# motor_board_tmc.net
KiCad netlist of a schematic drawn in EAGLE
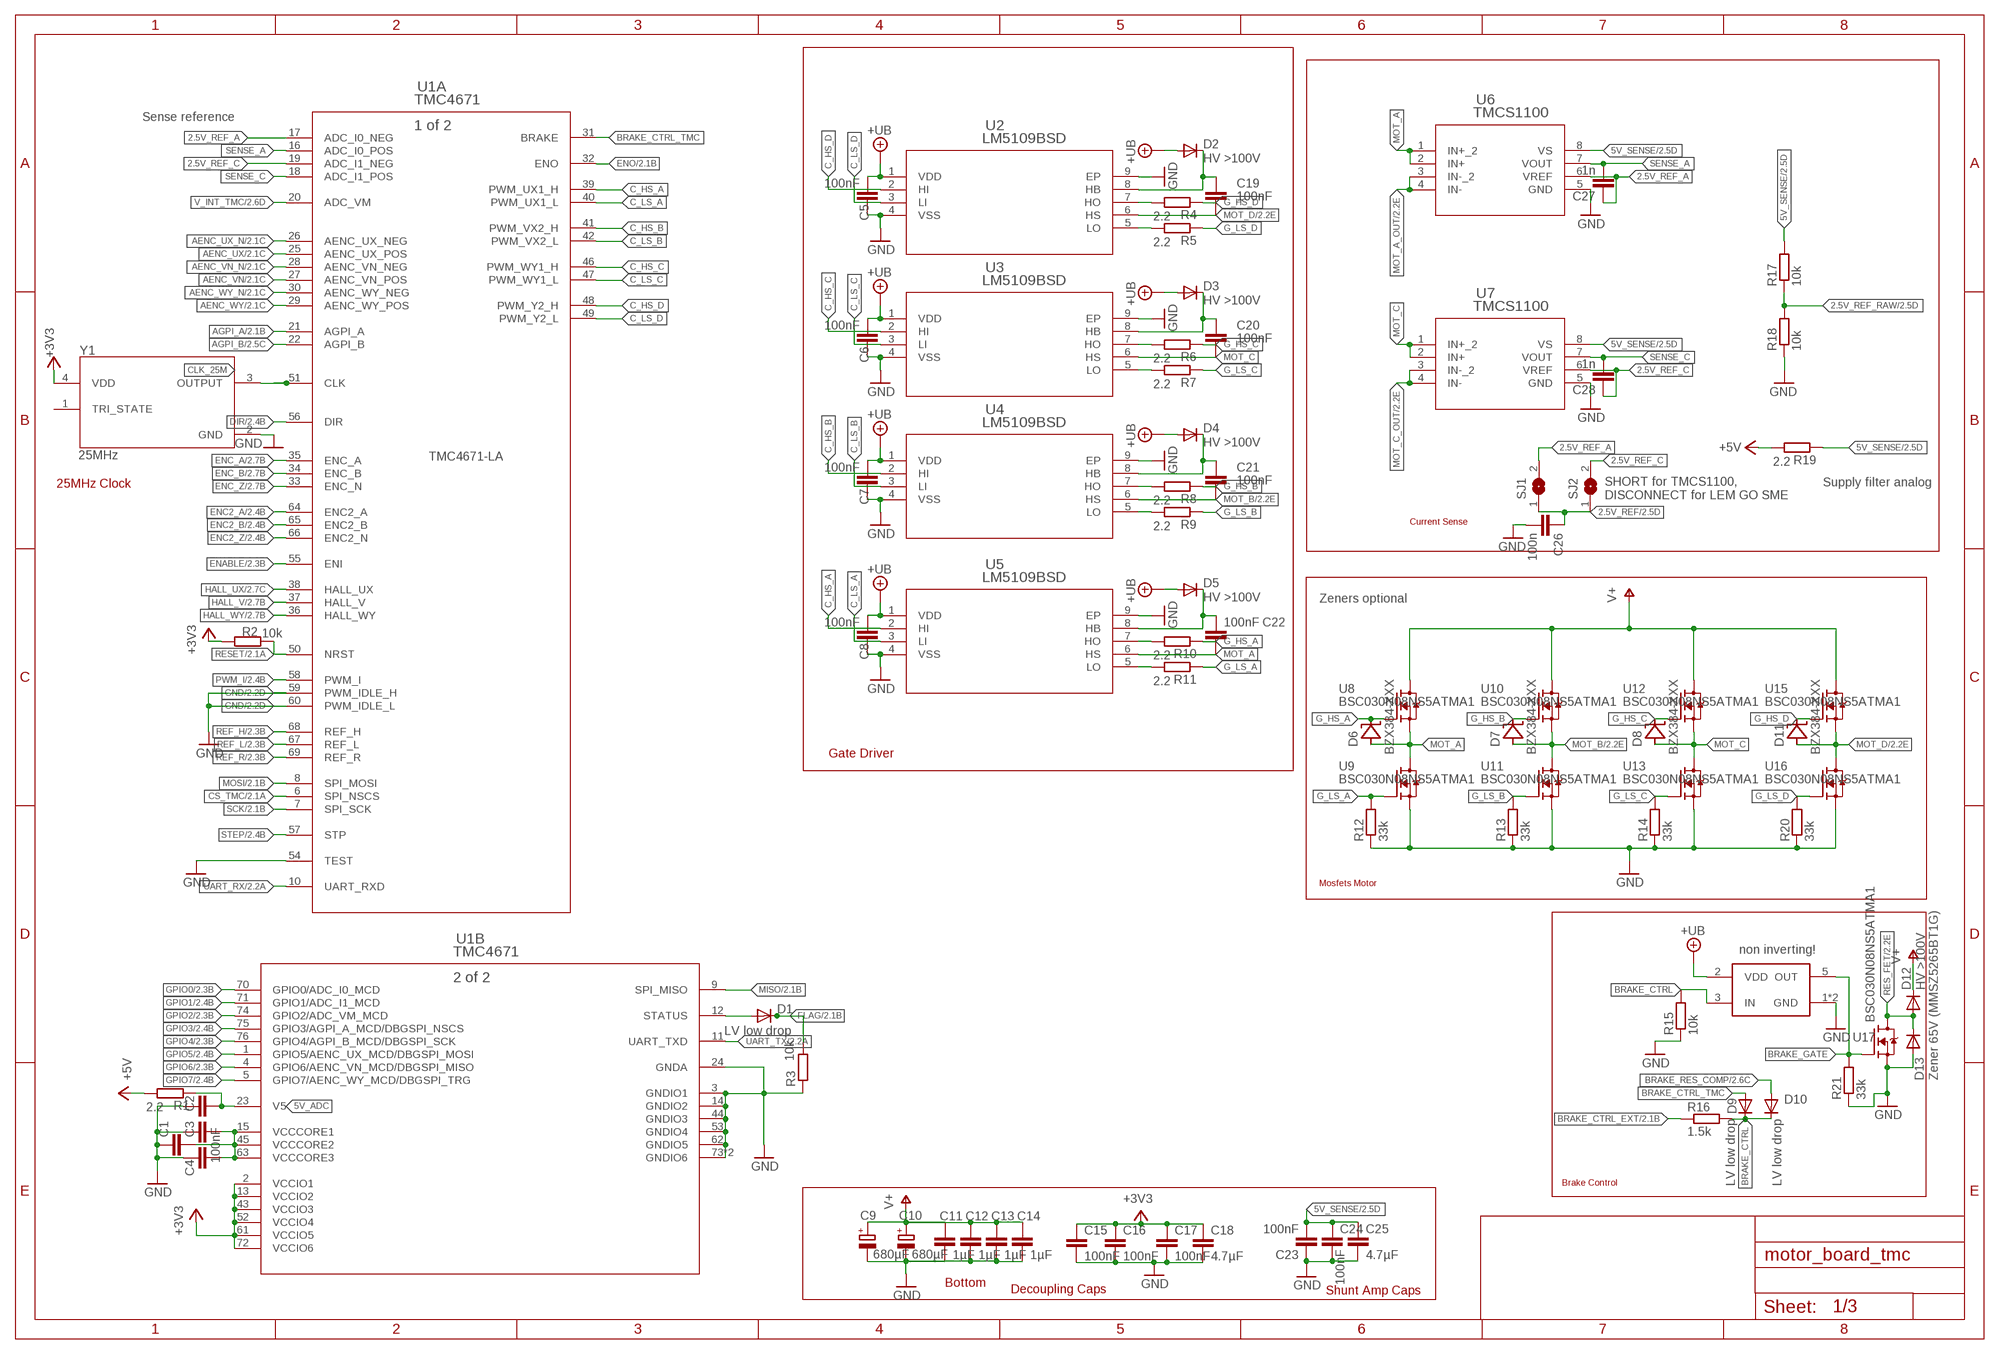
[diagram p0: schematic, sheet 1]
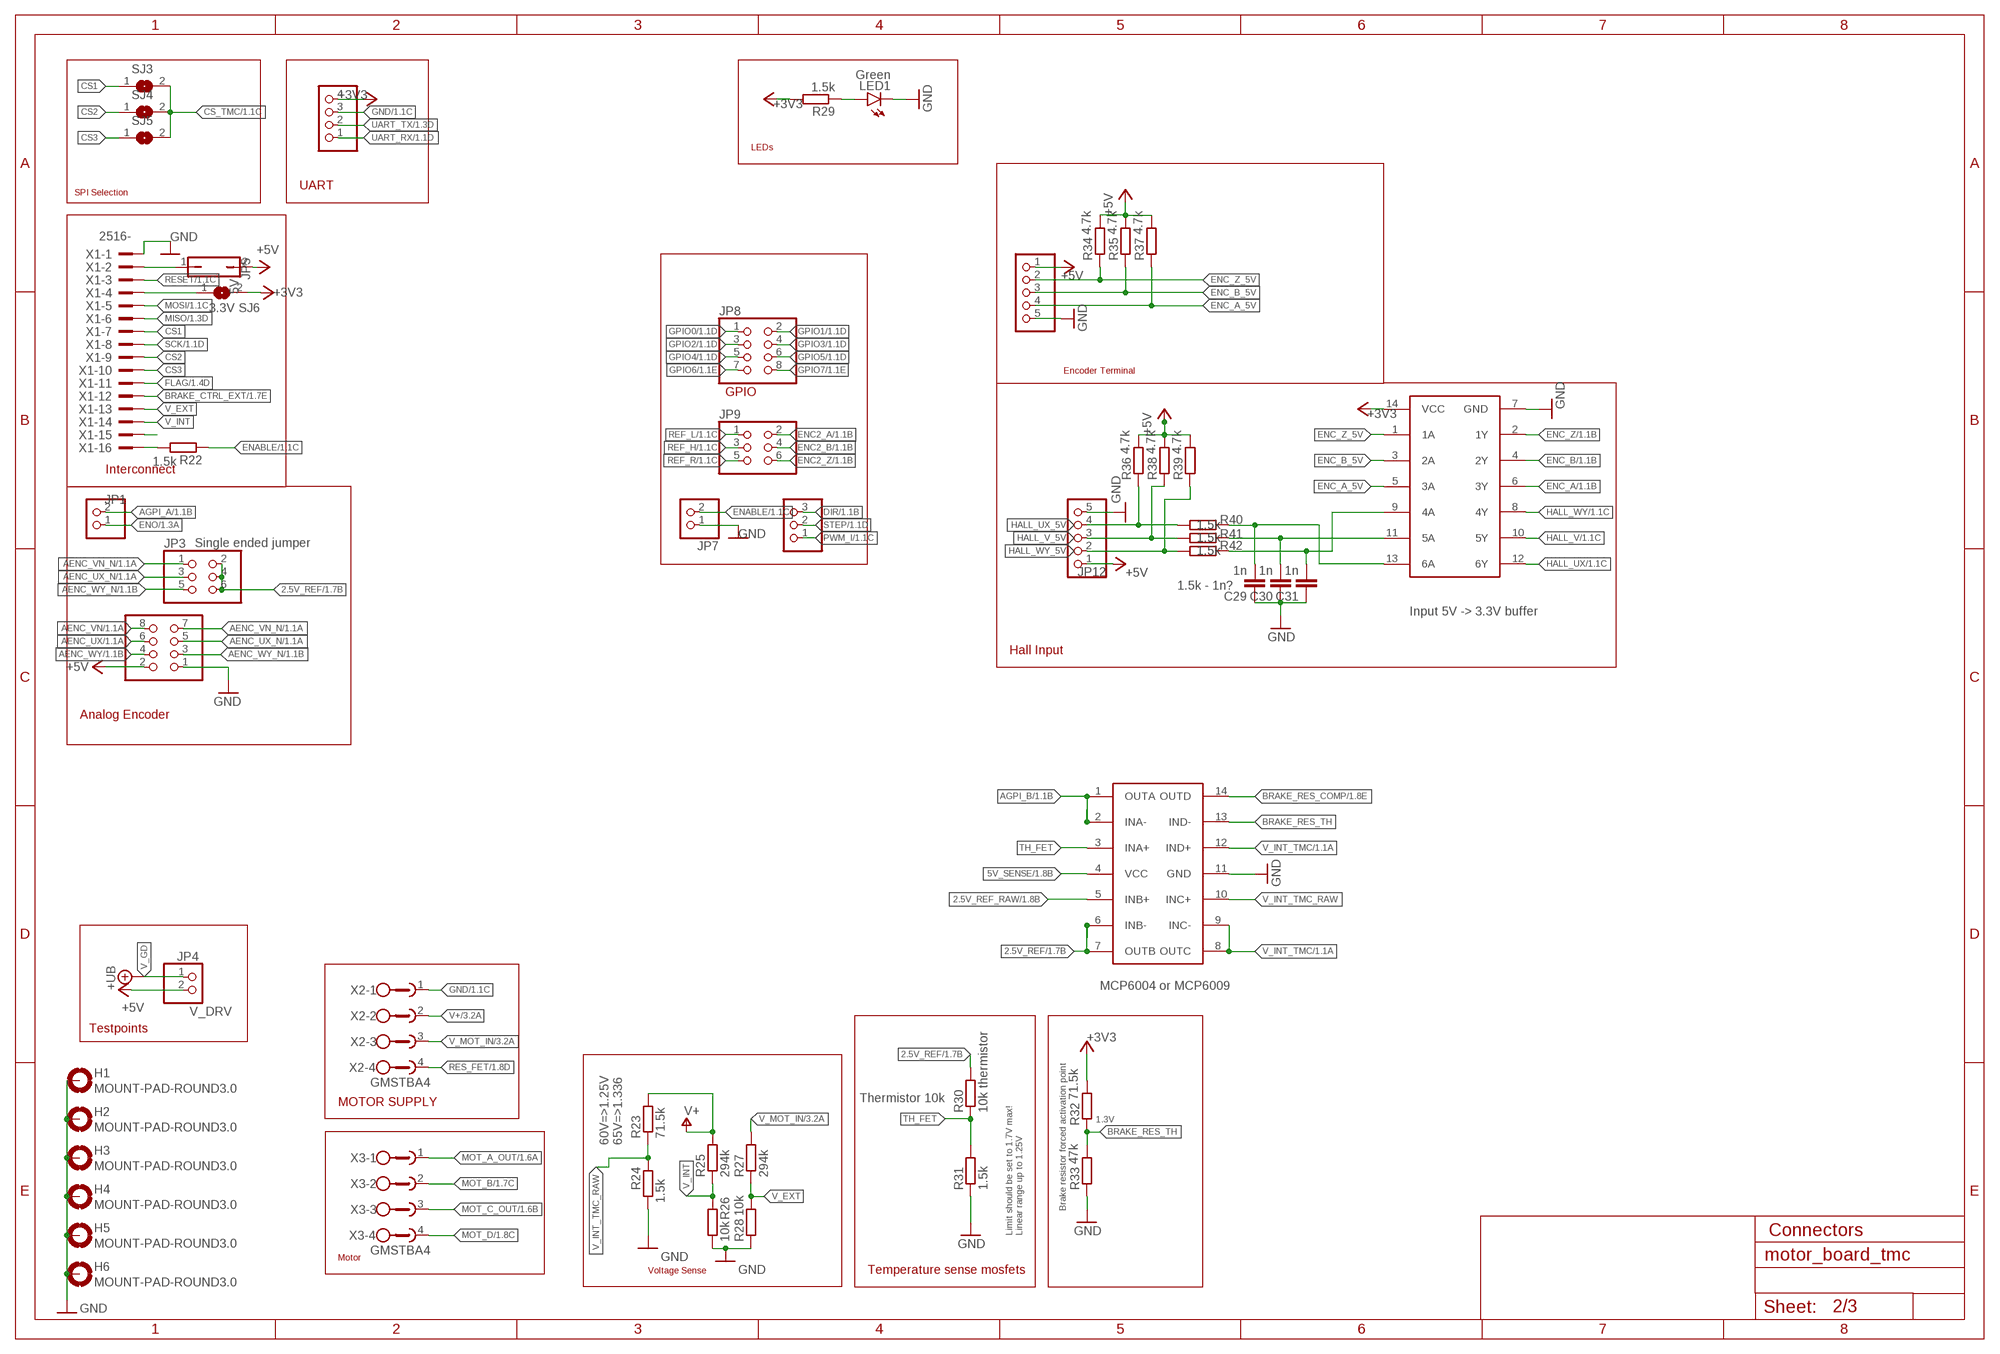
[diagram p1: schematic, sheet 2]
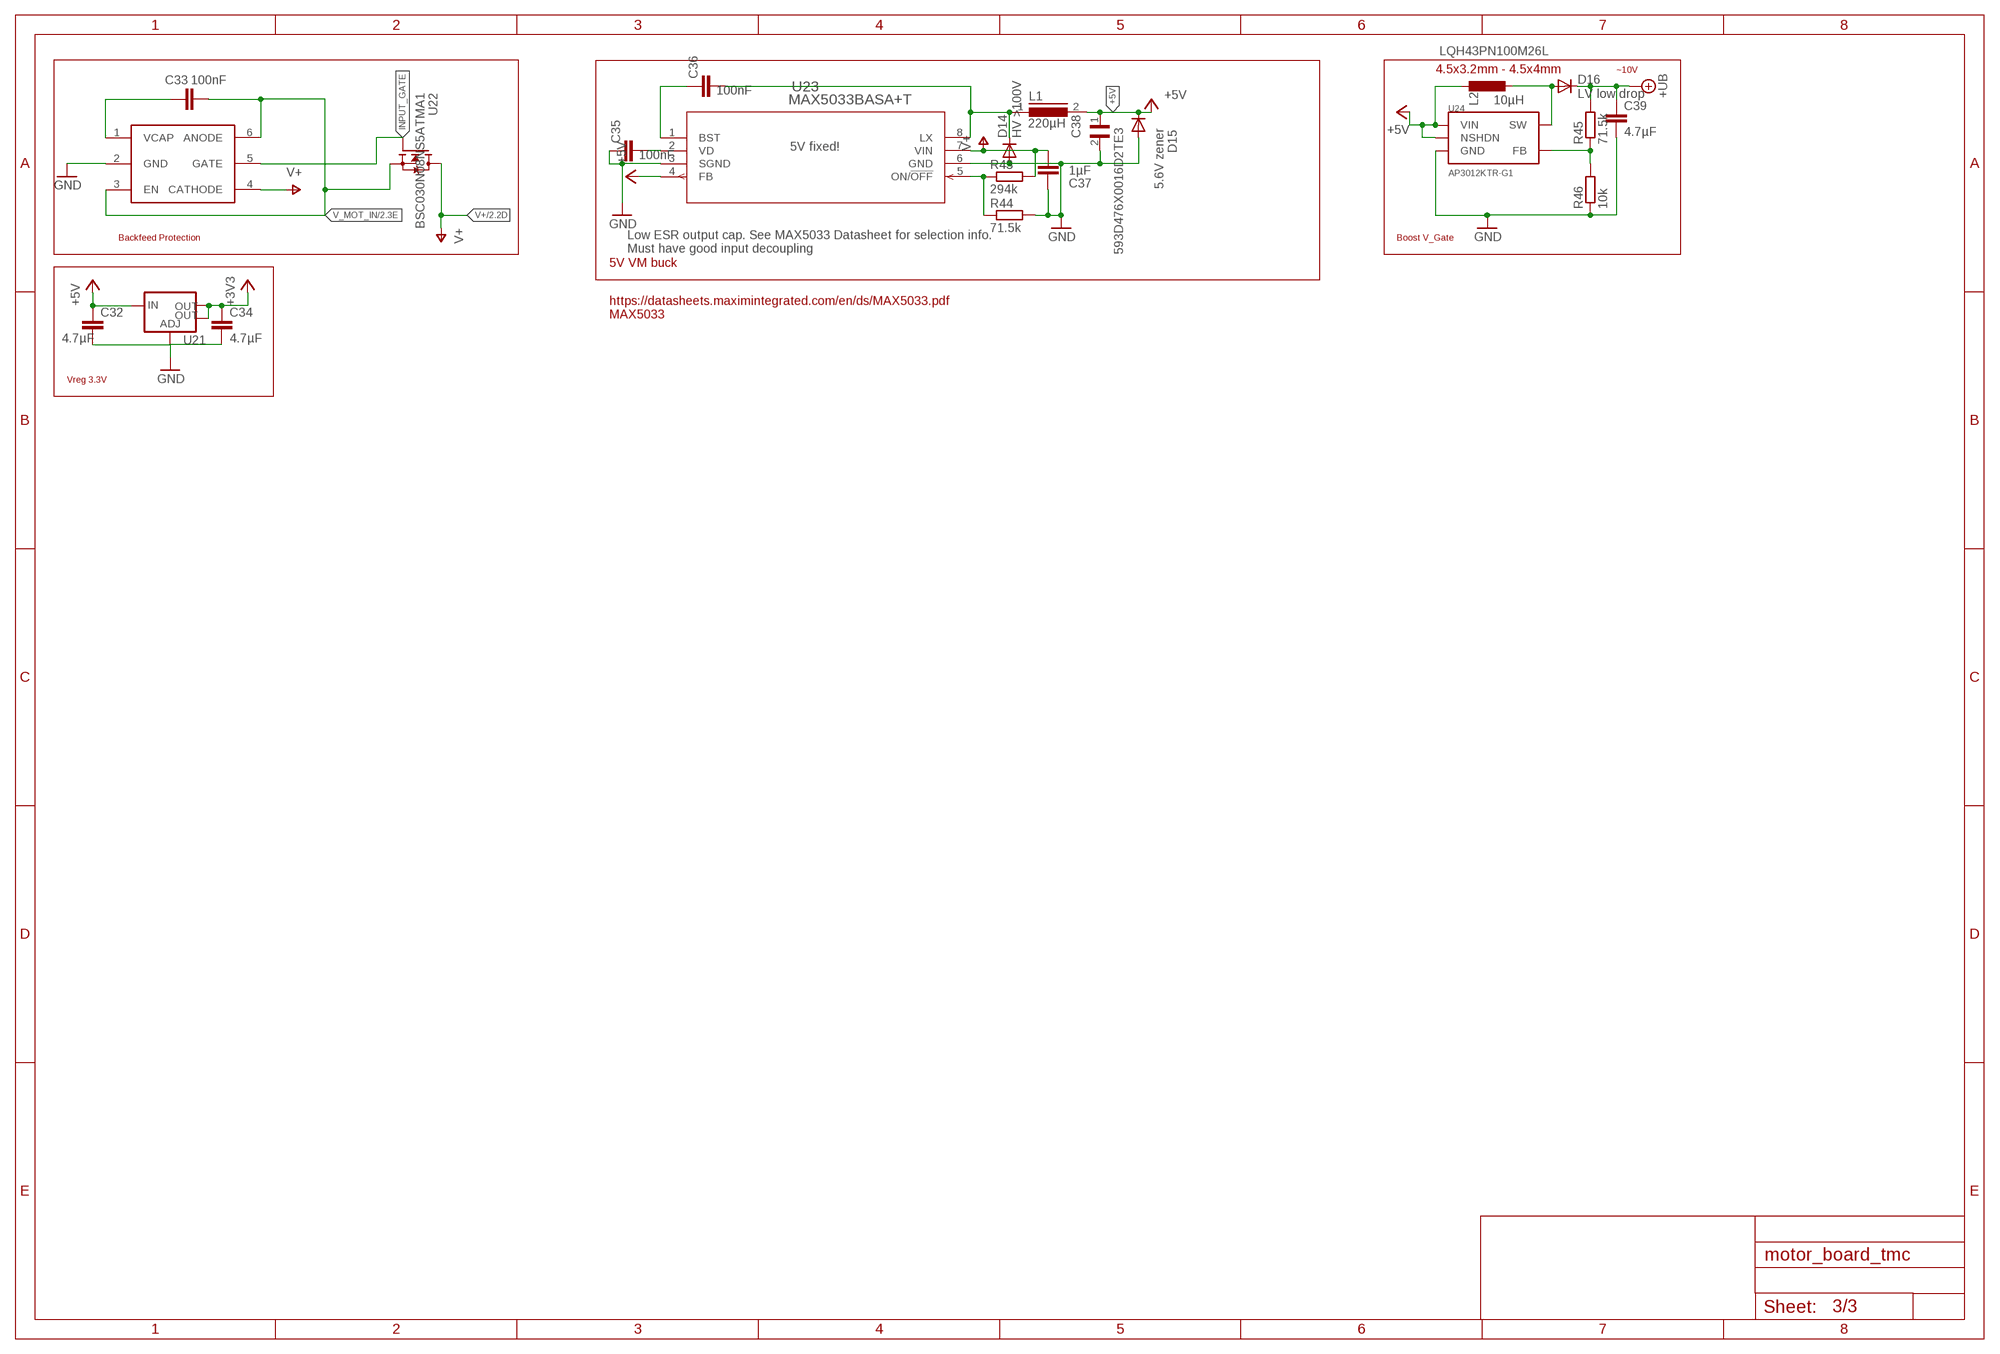
[diagram p2: schematic, sheet 3]

(export (version "E")
  (design (tool "Eeschema 10.0.6"))
  (components
    (comp (ref "C1")
      (value "100nF")
      (footprint "eagle-import:C0603")
      (libsource (lib "eagle-import") (part "C-EUC0603"))
    )
    (comp (ref "C2")
      (value "100nF")
      (footprint "eagle-import:C0603")
      (libsource (lib "eagle-import") (part "C-EUC0603"))
    )
    (comp (ref "C3")
      (value "100nF")
      (footprint "eagle-import:C0603")
      (libsource (lib "eagle-import") (part "C-EUC0603"))
    )
    (comp (ref "C4")
      (value "100nF")
      (footprint "eagle-import:C0603")
      (libsource (lib "eagle-import") (part "C-EUC0603"))
    )
    (comp (ref "C5")
      (value "100nF")
      (footprint "eagle-import:C0603")
      (libsource (lib "eagle-import") (part "C-EUC0603"))
    )
    (comp (ref "C6")
      (value "100nF")
      (footprint "eagle-import:C0603")
      (libsource (lib "eagle-import") (part "C-EUC0603"))
    )
    (comp (ref "C7")
      (value "100nF")
      (footprint "eagle-import:C0603")
      (libsource (lib "eagle-import") (part "C-EUC0603"))
    )
    (comp (ref "C8")
      (value "100nF")
      (footprint "eagle-import:C0603")
      (libsource (lib "eagle-import") (part "C-EUC0603"))
    )
    (comp (ref "C9")
      (value "680µF")
      (footprint "eagle-import:E7,5-16")
      (libsource (lib "eagle-import") (part "CPOL-EUE7.5-16"))
    )
    (comp (ref "C10")
      (value "680µF")
      (footprint "eagle-import:E7,5-16")
      (libsource (lib "eagle-import") (part "CPOL-EUE7.5-16"))
    )
    (comp (ref "C11")
      (value "1µF")
      (footprint "eagle-import:C1206")
      (libsource (lib "eagle-import") (part "C-EUC1206"))
    )
    (comp (ref "C12")
      (value "1µF")
      (footprint "eagle-import:C1206")
      (libsource (lib "eagle-import") (part "C-EUC1206"))
    )
    (comp (ref "C13")
      (value "1µF")
      (footprint "eagle-import:C1206")
      (libsource (lib "eagle-import") (part "C-EUC1206"))
    )
    (comp (ref "C14")
      (value "1µF")
      (footprint "eagle-import:C1206")
      (libsource (lib "eagle-import") (part "C-EUC1206"))
    )
    (comp (ref "C15")
      (value "100nF")
      (footprint "eagle-import:C0603")
      (libsource (lib "eagle-import") (part "C-EUC0603"))
    )
    (comp (ref "C16")
      (value "100nF")
      (footprint "eagle-import:C0603")
      (libsource (lib "eagle-import") (part "C-EUC0603"))
    )
    (comp (ref "C17")
      (value "100nF")
      (footprint "eagle-import:C0603")
      (libsource (lib "eagle-import") (part "C-EUC0603"))
    )
    (comp (ref "C18")
      (value "4.7µF")
      (footprint "eagle-import:C0805")
      (libsource (lib "eagle-import") (part "C-EUC0805"))
    )
    (comp (ref "C19")
      (value "100nF")
      (footprint "eagle-import:C0603")
      (libsource (lib "eagle-import") (part "C-EUC0603"))
    )
    (comp (ref "C20")
      (value "100nF")
      (footprint "eagle-import:C0603")
      (libsource (lib "eagle-import") (part "C-EUC0603"))
    )
    (comp (ref "C21")
      (value "100nF")
      (footprint "eagle-import:C0603")
      (libsource (lib "eagle-import") (part "C-EUC0603"))
    )
    (comp (ref "C22")
      (value "100nF")
      (footprint "eagle-import:C0603")
      (libsource (lib "eagle-import") (part "C-EUC0603"))
    )
    (comp (ref "C23")
      (value "100nF")
      (footprint "eagle-import:C0603")
      (libsource (lib "eagle-import") (part "C-EUC0603"))
    )
    (comp (ref "C24")
      (value "100nF")
      (footprint "eagle-import:C0603")
      (libsource (lib "eagle-import") (part "C-EUC0603"))
    )
    (comp (ref "C25")
      (value "4.7µF")
      (footprint "eagle-import:C0805")
      (libsource (lib "eagle-import") (part "C-EUC0805"))
    )
    (comp (ref "C26")
      (value "100n")
      (footprint "eagle-import:C0603")
      (libsource (lib "eagle-import") (part "C-EUC0603"))
    )
    (comp (ref "C27")
      (value "1n")
      (footprint "eagle-import:C0603")
      (libsource (lib "eagle-import") (part "C-EUC0603"))
    )
    (comp (ref "C28")
      (value "1n")
      (footprint "eagle-import:C0603")
      (libsource (lib "eagle-import") (part "C-EUC0603"))
    )
    (comp (ref "D1")
      (value "LV low drop")
      (footprint "eagle-import:SOD-123FL")
      (libsource (lib "eagle-import") (part "DIODE_SOD-123FL"))
    )
    (comp (ref "D2")
      (value "HV >100V")
      (footprint "eagle-import:SOD-123FL")
      (libsource (lib "eagle-import") (part "DIODE_SOD-123FL"))
    )
    (comp (ref "D3")
      (value "HV >100V")
      (footprint "eagle-import:SOD-123FL")
      (libsource (lib "eagle-import") (part "DIODE_SOD-123FL"))
    )
    (comp (ref "D4")
      (value "HV >100V")
      (footprint "eagle-import:SOD-123FL")
      (libsource (lib "eagle-import") (part "DIODE_SOD-123FL"))
    )
    (comp (ref "D5")
      (value "HV >100V")
      (footprint "eagle-import:SOD-123FL")
      (libsource (lib "eagle-import") (part "DIODE_SOD-123FL"))
    )
    (comp (ref "D6")
      (value "BZX384-XXX")
      (footprint "eagle-import:SOD323-R")
      (libsource (lib "eagle-import") (part "BZX384-XXX"))
    )
    (comp (ref "D7")
      (value "BZX384-XXX")
      (footprint "eagle-import:SOD323-R")
      (libsource (lib "eagle-import") (part "BZX384-XXX"))
    )
    (comp (ref "D8")
      (value "BZX384-XXX")
      (footprint "eagle-import:SOD323-R")
      (libsource (lib "eagle-import") (part "BZX384-XXX"))
    )
    (comp (ref "D9")
      (value "LV low drop")
      (footprint "eagle-import:SOD-123FL")
      (libsource (lib "eagle-import") (part "DIODE_SOD-123FL"))
    )
    (comp (ref "D10")
      (value "LV low drop")
      (footprint "eagle-import:SOD-123FL")
      (libsource (lib "eagle-import") (part "DIODE_SOD-123FL"))
    )
    (comp (ref "D11")
      (value "BZX384-XXX")
      (footprint "eagle-import:SOD323-R")
      (libsource (lib "eagle-import") (part "BZX384-XXX"))
    )
    (comp (ref "D12")
      (value "HV >100V")
      (footprint "eagle-import:SOD-123FL")
      (libsource (lib "eagle-import") (part "DIODE_SOD-123FL"))
    )
    (comp (ref "D13")
      (value "Zener 65V (MMSZ5265BT1G)")
      (footprint "eagle-import:SOD-123FL")
      (libsource (lib "eagle-import") (part "DIODE_SOD-123FL"))
    )
    (comp (ref "R1")
      (value "2.2")
      (footprint "eagle-import:R0603")
      (libsource (lib "eagle-import") (part "R-EU_R0603"))
    )
    (comp (ref "R2")
      (value "10k")
      (footprint "eagle-import:R0603")
      (libsource (lib "eagle-import") (part "R-EU_R0603"))
    )
    (comp (ref "R3")
      (value "10k")
      (footprint "eagle-import:R0603")
      (libsource (lib "eagle-import") (part "R-EU_R0603"))
    )
    (comp (ref "R4")
      (value "2.2")
      (footprint "eagle-import:R0603")
      (libsource (lib "eagle-import") (part "R-EU_R0603"))
    )
    (comp (ref "R5")
      (value "2.2")
      (footprint "eagle-import:R0603")
      (libsource (lib "eagle-import") (part "R-EU_R0603"))
    )
    (comp (ref "R6")
      (value "2.2")
      (footprint "eagle-import:R0603")
      (libsource (lib "eagle-import") (part "R-EU_R0603"))
    )
    (comp (ref "R7")
      (value "2.2")
      (footprint "eagle-import:R0603")
      (libsource (lib "eagle-import") (part "R-EU_R0603"))
    )
    (comp (ref "R8")
      (value "2.2")
      (footprint "eagle-import:R0603")
      (libsource (lib "eagle-import") (part "R-EU_R0603"))
    )
    (comp (ref "R9")
      (value "2.2")
      (footprint "eagle-import:R0603")
      (libsource (lib "eagle-import") (part "R-EU_R0603"))
    )
    (comp (ref "R10")
      (value "2.2")
      (footprint "eagle-import:R0603")
      (libsource (lib "eagle-import") (part "R-EU_R0603"))
    )
    (comp (ref "R11")
      (value "2.2")
      (footprint "eagle-import:R0603")
      (libsource (lib "eagle-import") (part "R-EU_R0603"))
    )
    (comp (ref "R12")
      (value "33k")
      (footprint "eagle-import:R0603")
      (libsource (lib "eagle-import") (part "R-EU_R0603"))
    )
    (comp (ref "R13")
      (value "33k")
      (footprint "eagle-import:R0603")
      (libsource (lib "eagle-import") (part "R-EU_R0603"))
    )
    (comp (ref "R14")
      (value "33k")
      (footprint "eagle-import:R0603")
      (libsource (lib "eagle-import") (part "R-EU_R0603"))
    )
    (comp (ref "R15")
      (value "10k")
      (footprint "eagle-import:R0603")
      (libsource (lib "eagle-import") (part "R-EU_R0603"))
    )
    (comp (ref "R16")
      (value "1.5k")
      (footprint "eagle-import:R0603")
      (libsource (lib "eagle-import") (part "R-EU_R0603"))
    )
    (comp (ref "R17")
      (value "10k")
      (footprint "eagle-import:R0603")
      (libsource (lib "eagle-import") (part "R-EU_R0603"))
    )
    (comp (ref "R18")
      (value "10k")
      (footprint "eagle-import:R0603")
      (libsource (lib "eagle-import") (part "R-EU_R0603"))
    )
    (comp (ref "R19")
      (value "2.2")
      (footprint "eagle-import:R0603")
      (libsource (lib "eagle-import") (part "R-EU_R0603"))
    )
    (comp (ref "R20")
      (value "33k")
      (footprint "eagle-import:R0603")
      (libsource (lib "eagle-import") (part "R-EU_R0603"))
    )
    (comp (ref "R21")
      (value "33k")
      (footprint "eagle-import:R0603")
      (libsource (lib "eagle-import") (part "R-EU_R0603"))
    )
    (comp (ref "SJ1") (value "SJ") (footprint "eagle-import:SJ") (libsource (lib "eagle-import") (part "SJ")))
    (comp (ref "SJ2") (value "SJ") (footprint "eagle-import:SJ") (libsource (lib "eagle-import") (part "SJ")))
    (comp (ref "U1")
      (value "TMC4671")
      (footprint "eagle-import:QFN76_10P5X6P5")
      (fields (field (name "MANUFACTURER_PART_NUMBER") "TMC4671ES"))
      (libsource (lib "eagle-import") (part "TMC4671"))
    )
    (comp (ref "U2")
      (value "LM5109BSD")
      (footprint "eagle-import:SDC08A")
      (fields (field (name "MANUFACTURER_PART_NUMBER") "lm5109bsd"))
      (libsource (lib "eagle-import") (part "LM5109BSD"))
    )
    (comp (ref "U3")
      (value "LM5109BSD")
      (footprint "eagle-import:SDC08A")
      (fields (field (name "MANUFACTURER_PART_NUMBER") "lm5109bsd"))
      (libsource (lib "eagle-import") (part "LM5109BSD"))
    )
    (comp (ref "U4")
      (value "LM5109BSD")
      (footprint "eagle-import:SDC08A")
      (fields (field (name "MANUFACTURER_PART_NUMBER") "lm5109bsd"))
      (libsource (lib "eagle-import") (part "LM5109BSD"))
    )
    (comp (ref "U5")
      (value "LM5109BSD")
      (footprint "eagle-import:SDC08A")
      (fields (field (name "MANUFACTURER_PART_NUMBER") "lm5109bsd"))
      (libsource (lib "eagle-import") (part "LM5109BSD"))
    )
    (comp (ref "U6")
      (value "TMCS1100")
      (footprint "eagle-import:SOIC8_D_TEX")
      (fields
        (field (name "MANUFACTURER_PART_NUMBER") "TMCS1100AxQDR")
        (field (name "COPYRIGHT") "Copyright (C) 2018 Accelerated Designs. All rights reserved")
      )
      (libsource (lib "eagle-import") (part "TMCS1100"))
    )
    (comp (ref "U7")
      (value "TMCS1100")
      (footprint "eagle-import:SOIC8_D_TEX")
      (fields
        (field (name "MANUFACTURER_PART_NUMBER") "TMCS1100AxQDR")
        (field (name "COPYRIGHT") "Copyright (C) 2018 Accelerated Designs. All rights reserved")
      )
      (libsource (lib "eagle-import") (part "TMCS1100"))
    )
    (comp (ref "U8")
      (value "BSC030N08NS5ATMA1")
      (footprint "eagle-import:MOSFET_BSC093N04LSGATMA1")
      (fields (field (name "MF") "Infineon Technologies"))
      (libsource (lib "eagle-import") (part "BSC030N08NS5ATMA1"))
    )
    (comp (ref "U9")
      (value "BSC030N08NS5ATMA1")
      (footprint "eagle-import:MOSFET_BSC093N04LSGATMA1")
      (fields (field (name "MF") "Infineon Technologies"))
      (libsource (lib "eagle-import") (part "BSC030N08NS5ATMA1"))
    )
    (comp (ref "U10")
      (value "BSC030N08NS5ATMA1")
      (footprint "eagle-import:MOSFET_BSC093N04LSGATMA1")
      (fields (field (name "MF") "Infineon Technologies"))
      (libsource (lib "eagle-import") (part "BSC030N08NS5ATMA1"))
    )
    (comp (ref "U11")
      (value "BSC030N08NS5ATMA1")
      (footprint "eagle-import:MOSFET_BSC093N04LSGATMA1")
      (fields (field (name "MF") "Infineon Technologies"))
      (libsource (lib "eagle-import") (part "BSC030N08NS5ATMA1"))
    )
    (comp (ref "U12")
      (value "BSC030N08NS5ATMA1")
      (footprint "eagle-import:MOSFET_BSC093N04LSGATMA1")
      (fields (field (name "MF") "Infineon Technologies"))
      (libsource (lib "eagle-import") (part "BSC030N08NS5ATMA1"))
    )
    (comp (ref "U13")
      (value "BSC030N08NS5ATMA1")
      (footprint "eagle-import:MOSFET_BSC093N04LSGATMA1")
      (fields (field (name "MF") "Infineon Technologies"))
      (libsource (lib "eagle-import") (part "BSC030N08NS5ATMA1"))
    )
    (comp (ref "U14")
      (value "MCP14XX")
      (footprint "eagle-import:SOT23-5L")
      (libsource (lib "eagle-import") (part "MCP14XX"))
    )
    (comp (ref "U15")
      (value "BSC030N08NS5ATMA1")
      (footprint "eagle-import:MOSFET_BSC093N04LSGATMA1")
      (fields (field (name "MF") "Infineon Technologies"))
      (libsource (lib "eagle-import") (part "BSC030N08NS5ATMA1"))
    )
    (comp (ref "U16")
      (value "BSC030N08NS5ATMA1")
      (footprint "eagle-import:MOSFET_BSC093N04LSGATMA1")
      (fields (field (name "MF") "Infineon Technologies"))
      (libsource (lib "eagle-import") (part "BSC030N08NS5ATMA1"))
    )
    (comp (ref "U17")
      (value "BSC030N08NS5ATMA1")
      (footprint "eagle-import:MOSFET_BSC093N04LSGATMA1")
      (fields (field (name "MF") "Infineon Technologies"))
      (libsource (lib "eagle-import") (part "BSC030N08NS5ATMA1"))
    )
    (comp (ref "Y1")
      (value "25MHz")
      (footprint "eagle-import:ECS-327KE-TR")
      (fields
        (field (name "DIGIKEY_PART_NUMBER") "XC1751TR-ND")
        (field (name "MANUFACTURER") "ECS Inc.")
        (field (name "MPN") "ECS-327KE-TR")
        (field (name "CREATED_BY") "PCBLayout.com")
      )
      (libsource (lib "eagle-import") (part "ECS-327KE-TR"))
    )
    (comp (ref "C29")
      (value "1n")
      (footprint "eagle-import:C0603")
      (libsource (lib "eagle-import") (part "C-EUC0603"))
    )
    (comp (ref "C30")
      (value "1n")
      (footprint "eagle-import:C0603")
      (libsource (lib "eagle-import") (part "C-EUC0603"))
    )
    (comp (ref "C31")
      (value "1n")
      (footprint "eagle-import:C0603")
      (libsource (lib "eagle-import") (part "C-EUC0603"))
    )
    (comp (ref "H1")
      (value "MOUNT-PAD-ROUND3.0")
      (footprint "eagle-import:3,0-PAD")
      (libsource (lib "eagle-import") (part "MOUNT-PAD-ROUND3.0"))
    )
    (comp (ref "H2")
      (value "MOUNT-PAD-ROUND3.0")
      (footprint "eagle-import:3,0-PAD")
      (libsource (lib "eagle-import") (part "MOUNT-PAD-ROUND3.0"))
    )
    (comp (ref "H3")
      (value "MOUNT-PAD-ROUND3.0")
      (footprint "eagle-import:3,0-PAD")
      (libsource (lib "eagle-import") (part "MOUNT-PAD-ROUND3.0"))
    )
    (comp (ref "H4")
      (value "MOUNT-PAD-ROUND3.0")
      (footprint "eagle-import:3,0-PAD")
      (libsource (lib "eagle-import") (part "MOUNT-PAD-ROUND3.0"))
    )
    (comp (ref "H5")
      (value "MOUNT-PAD-ROUND3.0")
      (footprint "eagle-import:3,0-PAD")
      (libsource (lib "eagle-import") (part "MOUNT-PAD-ROUND3.0"))
    )
    (comp (ref "H6")
      (value "MOUNT-PAD-ROUND3.0")
      (footprint "eagle-import:3,0-PAD")
      (libsource (lib "eagle-import") (part "MOUNT-PAD-ROUND3.0"))
    )
    (comp (ref "JP1")
      (value "PINHD-1X2")
      (footprint "eagle-import:1X02")
      (libsource (lib "eagle-import") (part "PINHD-1X2"))
    )
    (comp (ref "JP2")
      (value "PINHD-2X4")
      (footprint "eagle-import:2X04")
      (libsource (lib "eagle-import") (part "PINHD-2X4"))
    )
    (comp (ref "JP3")
      (value "PINHD-2X3")
      (footprint "eagle-import:2X03")
      (libsource (lib "eagle-import") (part "PINHD-2X3"))
    )
    (comp (ref "JP4")
      (value "V_DRV")
      (footprint "eagle-import:1X02")
      (libsource (lib "eagle-import") (part "PINHD-1X2"))
    )
    (comp (ref "JP5")
      (value "5V")
      (footprint "eagle-import:JP1")
      (libsource (lib "eagle-import") (part "JP1Q"))
    )
    (comp (ref "JP6")
      (value "PINHD-1X4")
      (footprint "eagle-import:1X04")
      (libsource (lib "eagle-import") (part "PINHD-1X4"))
    )
    (comp (ref "JP7")
      (value "PINHD-1X2")
      (footprint "eagle-import:1X02")
      (libsource (lib "eagle-import") (part "PINHD-1X2"))
    )
    (comp (ref "JP8")
      (value "PINHD-2X4")
      (footprint "eagle-import:2X04")
      (libsource (lib "eagle-import") (part "PINHD-2X4"))
    )
    (comp (ref "JP9")
      (value "PINHD-2X3")
      (footprint "eagle-import:2X03")
      (libsource (lib "eagle-import") (part "PINHD-2X3"))
    )
    (comp (ref "JP10")
      (value "PINHD-1X3")
      (footprint "eagle-import:1X03")
      (libsource (lib "eagle-import") (part "PINHD-1X3"))
    )
    (comp (ref "JP11")
      (value "PINHD-1X5")
      (footprint "eagle-import:1X05")
      (libsource (lib "eagle-import") (part "PINHD-1X5"))
    )
    (comp (ref "JP12")
      (value "PINHD-1X5")
      (footprint "eagle-import:1X05")
      (libsource (lib "eagle-import") (part "PINHD-1X5"))
    )
    (comp (ref "LED1")
      (value "Green")
      (footprint "eagle-import:SML0805")
      (libsource (lib "eagle-import") (part "LEDSML0805"))
    )
    (comp (ref "R22")
      (value "1.5k")
      (footprint "eagle-import:R0603")
      (libsource (lib "eagle-import") (part "R-EU_R0603"))
    )
    (comp (ref "R23")
      (value "71.5k")
      (footprint "eagle-import:R0805")
      (libsource (lib "eagle-import") (part "R-EU_R0805"))
    )
    (comp (ref "R24")
      (value "1.5k")
      (footprint "eagle-import:R0603")
      (libsource (lib "eagle-import") (part "R-EU_R0603"))
    )
    (comp (ref "R25")
      (value "294k")
      (footprint "eagle-import:R0805")
      (libsource (lib "eagle-import") (part "R-EU_R0805"))
    )
    (comp (ref "R26")
      (value "10k")
      (footprint "eagle-import:R0603")
      (libsource (lib "eagle-import") (part "R-EU_R0603"))
    )
    (comp (ref "R27")
      (value "294k")
      (footprint "eagle-import:R0805")
      (libsource (lib "eagle-import") (part "R-EU_R0805"))
    )
    (comp (ref "R28")
      (value "10k")
      (footprint "eagle-import:R0603")
      (libsource (lib "eagle-import") (part "R-EU_R0603"))
    )
    (comp (ref "R29")
      (value "1.5k")
      (footprint "eagle-import:R0603")
      (libsource (lib "eagle-import") (part "R-EU_R0603"))
    )
    (comp (ref "R30")
      (value "10k thermistor")
      (footprint "eagle-import:R0603")
      (libsource (lib "eagle-import") (part "R-EU_R0603"))
    )
    (comp (ref "R31")
      (value "1.5k")
      (footprint "eagle-import:R0603")
      (libsource (lib "eagle-import") (part "R-EU_R0603"))
    )
    (comp (ref "R32")
      (value "71.5k")
      (footprint "eagle-import:R0805")
      (libsource (lib "eagle-import") (part "R-EU_R0805"))
    )
    (comp (ref "R33")
      (value "47k")
      (footprint "eagle-import:R0603")
      (libsource (lib "eagle-import") (part "R-EU_R0603"))
    )
    (comp (ref "R34")
      (value "4.7k")
      (footprint "eagle-import:R0603")
      (libsource (lib "eagle-import") (part "R-EU_R0603"))
    )
    (comp (ref "R35")
      (value "4.7k")
      (footprint "eagle-import:R0603")
      (libsource (lib "eagle-import") (part "R-EU_R0603"))
    )
    (comp (ref "R36")
      (value "4.7k")
      (footprint "eagle-import:R0603")
      (libsource (lib "eagle-import") (part "R-EU_R0603"))
    )
    (comp (ref "R37")
      (value "4.7k")
      (footprint "eagle-import:R0603")
      (libsource (lib "eagle-import") (part "R-EU_R0603"))
    )
    (comp (ref "R38")
      (value "4.7k")
      (footprint "eagle-import:R0603")
      (libsource (lib "eagle-import") (part "R-EU_R0603"))
    )
    (comp (ref "R39")
      (value "4.7k")
      (footprint "eagle-import:R0603")
      (libsource (lib "eagle-import") (part "R-EU_R0603"))
    )
    (comp (ref "R40")
      (value "1.5k")
      (footprint "eagle-import:R0603")
      (libsource (lib "eagle-import") (part "R-EU_R0603"))
    )
    (comp (ref "R41")
      (value "1.5k")
      (footprint "eagle-import:R0603")
      (libsource (lib "eagle-import") (part "R-EU_R0603"))
    )
    (comp (ref "R42")
      (value "1.5k")
      (footprint "eagle-import:R0603")
      (libsource (lib "eagle-import") (part "R-EU_R0603"))
    )
    (comp (ref "SJ3") (value "SJ") (footprint "eagle-import:SJ") (libsource (lib "eagle-import") (part "SJ")))
    (comp (ref "SJ4") (value "SJ") (footprint "eagle-import:SJ") (libsource (lib "eagle-import") (part "SJ")))
    (comp (ref "SJ5") (value "SJ") (footprint "eagle-import:SJ") (libsource (lib "eagle-import") (part "SJ")))
    (comp (ref "SJ6")
      (value "3.3V")
      (footprint "eagle-import:SJ")
      (libsource (lib "eagle-import") (part "SJ"))
    )
    (comp (ref "U18")
      (value "MCP6004")
      (footprint "eagle-import:TSSOP14")
      (libsource (lib "eagle-import") (part "MCP6004"))
    )
    (comp (ref "U19")
      (value "74LV17APWJ")
      (footprint "eagle-import:TSSOP14")
      (libsource (lib "eagle-import") (part "74LV17APWJ"))
    )
    (comp (ref "X1")
      (value "2516-")
      (footprint "eagle-import:PAK100_2500-16")
      (libsource (lib "eagle-import") (part "2516-"))
    )
    (comp (ref "X2")
      (value "GMSTBA4")
      (footprint "eagle-import:GMSTBA4")
      (fields (field (name "MF") "FARNELL") (field (name "MPN") "1757268"))
      (libsource (lib "eagle-import") (part "GMSTBA4"))
    )
    (comp (ref "X3")
      (value "GMSTBA4")
      (footprint "eagle-import:GMSTBA4")
      (fields (field (name "MF") "FARNELL") (field (name "MPN") "1757268"))
      (libsource (lib "eagle-import") (part "GMSTBA4"))
    )
    (comp (ref "C32")
      (value "4.7µF")
      (footprint "eagle-import:C0805")
      (libsource (lib "eagle-import") (part "C-EUC0805"))
    )
    (comp (ref "C33")
      (value "100nF")
      (footprint "eagle-import:C0603")
      (libsource (lib "eagle-import") (part "C-EUC0603"))
    )
    (comp (ref "C34")
      (value "4.7µF")
      (footprint "eagle-import:C0805")
      (libsource (lib "eagle-import") (part "C-EUC0805"))
    )
    (comp (ref "C35")
      (value "100nF")
      (footprint "eagle-import:C0603")
      (libsource (lib "eagle-import") (part "C-EUC0603"))
    )
    (comp (ref "C36")
      (value "100nF")
      (footprint "eagle-import:C0603")
      (libsource (lib "eagle-import") (part "C-EUC0603"))
    )
    (comp (ref "C37")
      (value "1µF")
      (footprint "eagle-import:C1206")
      (libsource (lib "eagle-import") (part "C-EUC1206"))
    )
    (comp (ref "C38")
      (value "593D476X0016D2TE3")
      (footprint "eagle-import:CAPPM7343X310N")
      (fields (field (name "DIGI-KEY_PART_NUMBER") "718-2142-1-ND") (field (name "MF") "Vishay Sprague"))
      (libsource (lib "eagle-import") (part "593D476X0016D2TE3"))
    )
    (comp (ref "C39")
      (value "4.7µF")
      (footprint "eagle-import:C0805")
      (libsource (lib "eagle-import") (part "C-EUC0805"))
    )
    (comp (ref "D14")
      (value "HV >100V")
      (footprint "eagle-import:SOD-123FL")
      (libsource (lib "eagle-import") (part "DIODE_SOD-123FL"))
    )
    (comp (ref "D15")
      (value "5.6V zener")
      (footprint "eagle-import:SOD-123FL")
      (libsource (lib "eagle-import") (part "DIODE_SOD-123FL"))
    )
    (comp (ref "D16")
      (value "LV low drop")
      (footprint "eagle-import:SOD-123FL")
      (libsource (lib "eagle-import") (part "DIODE_SOD-123FL"))
    )
    (comp (ref "L1")
      (value "220µH")
      (footprint "eagle-import:8MMINDUCTOR")
      (libsource (lib "eagle-import") (part "8MMINDUCTOR"))
    )
    (comp (ref "L2")
      (value "10µH")
      (footprint "eagle-import:L4532P")
      (libsource (lib "eagle-import") (part "L-EUL4532P"))
    )
    (comp (ref "R43")
      (value "294k")
      (footprint "eagle-import:R0805")
      (libsource (lib "eagle-import") (part "R-EU_R0805"))
    )
    (comp (ref "R44")
      (value "71.5k")
      (footprint "eagle-import:R0805")
      (libsource (lib "eagle-import") (part "R-EU_R0805"))
    )
    (comp (ref "R45")
      (value "71.5k")
      (footprint "eagle-import:R0805")
      (libsource (lib "eagle-import") (part "R-EU_R0805"))
    )
    (comp (ref "R46")
      (value "10k")
      (footprint "eagle-import:R0603")
      (libsource (lib "eagle-import") (part "R-EU_R0603"))
    )
    (comp (ref "U20")
      (value "LM74700-Q1")
      (footprint "eagle-import:SOT23-6")
      (libsource (lib "eagle-import") (part "LM74700-Q1"))
    )
    (comp (ref "U21")
      (value "V_REG_LM1117SOT223")
      (footprint "eagle-import:SOT223")
      (libsource (lib "eagle-import") (part "V_REG_LM1117SOT223"))
    )
    (comp (ref "U22")
      (value "BSC030N08NS5ATMA1")
      (footprint "eagle-import:MOSFET_BSC093N04LSGATMA1")
      (fields (field (name "MF") "Infineon Technologies"))
      (libsource (lib "eagle-import") (part "BSC030N08NS5ATMA1"))
    )
    (comp (ref "U23")
      (value "MAX5033BASA+T")
      (footprint "eagle-import:21-0041B_8_MXM")
      (fields (field (name "MANUFACTURER_PART_NUMBER") "max5033basa+T"))
      (libsource (lib "eagle-import") (part "MAX5033BASA+T"))
    )
    (comp (ref "U24")
      (value "AP3012KTR-G1")
      (footprint "eagle-import:SOT23-5L")
      (libsource (lib "eagle-import") (part "AP3012KTR-G1"))
    )
  )
  (nets
    (net (code "1") (name "+3V3") (class "Default")
      (node (ref "C15") (pin "1") (pinfunction "1_1") (pintype "passive"))
      (node (ref "C16") (pin "1") (pinfunction "1_1") (pintype "passive"))
      (node (ref "C17") (pin "1") (pinfunction "1_1") (pintype "passive"))
      (node (ref "C18") (pin "1") (pinfunction "1_1") (pintype "passive"))
      (node (ref "C34") (pin "1") (pinfunction "1_1") (pintype "passive"))
      (node (ref "JP6") (pin "4") (pinfunction "4_4") (pintype "passive"))
      (node (ref "R2") (pin "2") (pinfunction "2_2") (pintype "passive"))
      (node (ref "R29") (pin "2") (pinfunction "2_2") (pintype "passive"))
      (node (ref "R32") (pin "2") (pinfunction "2_2") (pintype "passive"))
      (node (ref "SJ6") (pin "2") (pinfunction "2_2") (pintype "passive"))
      (node (ref "U1") (pin "13") (pinfunction "VCCIO2_13") (pintype "power_in"))
      (node (ref "U1") (pin "2") (pinfunction "VCCIO1_2") (pintype "power_in"))
      (node (ref "U1") (pin "43") (pinfunction "VCCIO3_43") (pintype "power_in"))
      (node (ref "U1") (pin "52") (pinfunction "VCCIO4_52") (pintype "power_in"))
      (node (ref "U1") (pin "61") (pinfunction "VCCIO5_61") (pintype "power_in"))
      (node (ref "U1") (pin "72") (pinfunction "VCCIO6_72") (pintype "power_in"))
      (node (ref "U19") (pin "14") (pinfunction "VCC_14") (pintype "bidirectional"))
      (node (ref "U21") (pin "2") (pinfunction "OUT_2") (pintype "output"))
      (node (ref "U21") (pin "4") (pinfunction "OUT_4") (pintype "output"))
      (node (ref "Y1") (pin "4") (pinfunction "VDD_4") (pintype "power_in"))
    )
    (net (code "2") (name "+5V") (class "Default")
      (node (ref "C32") (pin "1") (pinfunction "1_1") (pintype "passive"))
      (node (ref "C38") (pin "1") (pinfunction "1_1") (pintype "passive"))
      (node (ref "D15") (pin "C") (pinfunction "C_C") (pintype "passive"))
      (node (ref "JP11") (pin "1") (pinfunction "1_1") (pintype "passive"))
      (node (ref "JP12") (pin "1") (pinfunction "1_1") (pintype "passive"))
      (node (ref "JP2") (pin "2") (pinfunction "2_2") (pintype "passive"))
      (node (ref "JP4") (pin "2") (pinfunction "2_2") (pintype "passive"))
      (node (ref "JP5") (pin "2") (pinfunction "2_2") (pintype "passive"))
      (node (ref "L1") (pin "2") (pinfunction "2_2") (pintype "passive"))
      (node (ref "L2") (pin "1") (pinfunction "1_1") (pintype "passive"))
      (node (ref "R1") (pin "2") (pinfunction "2_2") (pintype "passive"))
      (node (ref "R19") (pin "2") (pinfunction "2_2") (pintype "passive"))
      (node (ref "R34") (pin "2") (pinfunction "2_2") (pintype "passive"))
      (node (ref "R35") (pin "2") (pinfunction "2_2") (pintype "passive"))
      (node (ref "R36") (pin "2") (pinfunction "2_2") (pintype "passive"))
      (node (ref "R37") (pin "2") (pinfunction "2_2") (pintype "passive"))
      (node (ref "R38") (pin "2") (pinfunction "2_2") (pintype "passive"))
      (node (ref "R39") (pin "2") (pinfunction "2_2") (pintype "passive"))
      (node (ref "U21") (pin "3") (pinfunction "IN_3") (pintype "input"))
      (node (ref "U23") (pin "4") (pinfunction "FB_4") (pintype "output"))
      (node (ref "U24") (pin "4") (pinfunction "NSHDN_4") (pintype "bidirectional"))
      (node (ref "U24") (pin "5") (pinfunction "VIN_5") (pintype "bidirectional"))
    )
    (net (code "3") (name "2.5V_REF") (class "Default")
      (node (ref "C26") (pin "1") (pinfunction "1_1") (pintype "passive"))
      (node (ref "JP3") (pin "2") (pinfunction "2_2") (pintype "passive"))
      (node (ref "JP3") (pin "4") (pinfunction "4_4") (pintype "passive"))
      (node (ref "JP3") (pin "6") (pinfunction "6_6") (pintype "passive"))
      (node (ref "R30") (pin "2") (pinfunction "2_2") (pintype "passive"))
      (node (ref "SJ1") (pin "1") (pinfunction "1_1") (pintype "passive"))
      (node (ref "SJ2") (pin "1") (pinfunction "1_1") (pintype "passive"))
      (node (ref "U18") (pin "6") (pinfunction "INB-_6") (pintype "bidirectional"))
      (node (ref "U18") (pin "7") (pinfunction "OUTB_7") (pintype "bidirectional"))
    )
    (net (code "4") (name "2.5V_REF_A") (class "Default")
      (node (ref "C27") (pin "1") (pinfunction "1_1") (pintype "passive"))
      (node (ref "SJ1") (pin "2") (pinfunction "2_2") (pintype "passive"))
      (node (ref "U1") (pin "17") (pinfunction "ADC_I0_NEG_17") (pintype "input"))
      (node (ref "U6") (pin "6") (pinfunction "VREF_6") (pintype "power_in"))
    )
    (net (code "5") (name "2.5V_REF_C") (class "Default")
      (node (ref "C28") (pin "1") (pinfunction "1_1") (pintype "passive"))
      (node (ref "SJ2") (pin "2") (pinfunction "2_2") (pintype "passive"))
      (node (ref "U1") (pin "19") (pinfunction "ADC_I1_NEG_19") (pintype "input"))
      (node (ref "U7") (pin "6") (pinfunction "VREF_6") (pintype "power_in"))
    )
    (net (code "6") (name "2.5V_REF_RAW") (class "Default")
      (node (ref "R17") (pin "1") (pinfunction "1_1") (pintype "passive"))
      (node (ref "R18") (pin "2") (pinfunction "2_2") (pintype "passive"))
      (node (ref "U18") (pin "5") (pinfunction "INB+_5") (pintype "bidirectional"))
    )
    (net (code "7") (name "5V_ADC") (class "Default")
      (node (ref "C2") (pin "2") (pinfunction "2_2") (pintype "passive"))
      (node (ref "R1") (pin "1") (pinfunction "1_1") (pintype "passive"))
      (node (ref "U1") (pin "23") (pinfunction "V5_23") (pintype "power_in"))
    )
    (net (code "8") (name "5V_SENSE") (class "Default")
      (node (ref "C23") (pin "2") (pinfunction "2_2") (pintype "passive"))
      (node (ref "C24") (pin "1") (pinfunction "1_1") (pintype "passive"))
      (node (ref "C25") (pin "1") (pinfunction "1_1") (pintype "passive"))
      (node (ref "R17") (pin "2") (pinfunction "2_2") (pintype "passive"))
      (node (ref "R19") (pin "1") (pinfunction "1_1") (pintype "passive"))
      (node (ref "U18") (pin "4") (pinfunction "VCC_4") (pintype "bidirectional"))
      (node (ref "U6") (pin "8") (pinfunction "VS_8") (pintype "power_in"))
      (node (ref "U7") (pin "8") (pinfunction "VS_8") (pintype "power_in"))
    )
    (net (code "9") (name "AENC_UX") (class "Default")
      (node (ref "JP2") (pin "6") (pinfunction "6_6") (pintype "passive"))
      (node (ref "U1") (pin "25") (pinfunction "AENC_UX_POS_25") (pintype "input"))
    )
    (net (code "10") (name "AENC_UX_N") (class "Default")
      (node (ref "JP2") (pin "5") (pinfunction "5_5") (pintype "passive"))
      (node (ref "JP3") (pin "3") (pinfunction "3_3") (pintype "passive"))
      (node (ref "U1") (pin "26") (pinfunction "AENC_UX_NEG_26") (pintype "input"))
    )
    (net (code "11") (name "AENC_VN") (class "Default")
      (node (ref "JP2") (pin "8") (pinfunction "8_8") (pintype "passive"))
      (node (ref "U1") (pin "27") (pinfunction "AENC_VN_POS_27") (pintype "input"))
    )
    (net (code "12") (name "AENC_VN_N") (class "Default")
      (node (ref "JP2") (pin "7") (pinfunction "7_7") (pintype "passive"))
      (node (ref "JP3") (pin "1") (pinfunction "1_1") (pintype "passive"))
      (node (ref "U1") (pin "28") (pinfunction "AENC_VN_NEG_28") (pintype "input"))
    )
    (net (code "13") (name "AENC_WY") (class "Default")
      (node (ref "JP2") (pin "4") (pinfunction "4_4") (pintype "passive"))
      (node (ref "U1") (pin "29") (pinfunction "AENC_WY_POS_29") (pintype "input"))
    )
    (net (code "14") (name "AENC_WY_N") (class "Default")
      (node (ref "JP2") (pin "3") (pinfunction "3_3") (pintype "passive"))
      (node (ref "JP3") (pin "5") (pinfunction "5_5") (pintype "passive"))
      (node (ref "U1") (pin "30") (pinfunction "AENC_WY_NEG_30") (pintype "input"))
    )
    (net (code "15") (name "AGPI_A") (class "Default")
      (node (ref "JP1") (pin "2") (pinfunction "2_2") (pintype "passive"))
      (node (ref "U1") (pin "21") (pinfunction "AGPI_A_21") (pintype "input"))
    )
    (net (code "16") (name "AGPI_B") (class "Default")
      (node (ref "U1") (pin "22") (pinfunction "AGPI_B_22") (pintype "input"))
      (node (ref "U18") (pin "1") (pinfunction "OUTA_1") (pintype "bidirectional"))
      (node (ref "U18") (pin "2") (pinfunction "INA-_2") (pintype "bidirectional"))
    )
    (net (code "17") (name "BRAKE_CTRL") (class "Default")
      (node (ref "D10") (pin "C") (pinfunction "C_C") (pintype "passive"))
      (node (ref "D9") (pin "C") (pinfunction "C_C") (pintype "passive"))
      (node (ref "R15") (pin "2") (pinfunction "2_2") (pintype "passive"))
      (node (ref "R16") (pin "2") (pinfunction "2_2") (pintype "passive"))
      (node (ref "U14") (pin "3") (pinfunction "IN_3") (pintype "bidirectional"))
    )
    (net (code "18") (name "BRAKE_CTRL_EXT") (class "Default")
      (node (ref "R16") (pin "1") (pinfunction "1_1") (pintype "passive"))
      (node (ref "X1") (pin "12") (pinfunction "KL_12") (pintype "passive"))
    )
    (net (code "19") (name "BRAKE_CTRL_TMC") (class "Default")
      (node (ref "D9") (pin "A") (pinfunction "A_A") (pintype "passive"))
      (node (ref "U1") (pin "31") (pinfunction "BRAKE_31") (pintype "output"))
    )
    (net (code "20") (name "BRAKE_GATE") (class "Default")
      (node (ref "R21") (pin "2") (pinfunction "2_2") (pintype "passive"))
      (node (ref "U14") (pin "5") (pinfunction "OUT_5") (pintype "bidirectional"))
      (node (ref "U17") (pin "4") (pinfunction "G_4") (pintype "passive"))
    )
    (net (code "21") (name "BRAKE_RES_COMP") (class "Default")
      (node (ref "D10") (pin "A") (pinfunction "A_A") (pintype "passive"))
      (node (ref "U18") (pin "14") (pinfunction "OUTD_14") (pintype "bidirectional"))
    )
    (net (code "22") (name "BRAKE_RES_TH") (class "Default")
      (node (ref "R32") (pin "1") (pinfunction "1_1") (pintype "passive"))
      (node (ref "R33") (pin "2") (pinfunction "2_2") (pintype "passive"))
      (node (ref "U18") (pin "13") (pinfunction "IND-_13") (pintype "bidirectional"))
    )
    (net (code "23") (name "CLK_25M") (class "Default")
      (node (ref "U1") (pin "51") (pinfunction "CLK_51") (pintype "input"))
      (node (ref "Y1") (pin "3") (pinfunction "OUTPUT_3") (pintype "output"))
    )
    (net (code "24") (name "CS1") (class "Default")
      (node (ref "SJ3") (pin "1") (pinfunction "1_1") (pintype "passive"))
      (node (ref "X1") (pin "7") (pinfunction "KL_7") (pintype "passive"))
    )
    (net (code "25") (name "CS2") (class "Default")
      (node (ref "SJ4") (pin "1") (pinfunction "1_1") (pintype "passive"))
      (node (ref "X1") (pin "9") (pinfunction "KL_9") (pintype "passive"))
    )
    (net (code "26") (name "CS3") (class "Default")
      (node (ref "SJ5") (pin "1") (pinfunction "1_1") (pintype "passive"))
      (node (ref "X1") (pin "10") (pinfunction "KL_10") (pintype "passive"))
    )
    (net (code "27") (name "CS_TMC") (class "Default")
      (node (ref "SJ3") (pin "2") (pinfunction "2_2") (pintype "passive"))
      (node (ref "SJ4") (pin "2") (pinfunction "2_2") (pintype "passive"))
      (node (ref "SJ5") (pin "2") (pinfunction "2_2") (pintype "passive"))
      (node (ref "U1") (pin "6") (pinfunction "SPI_NSCS_6") (pintype "input"))
    )
    (net (code "28") (name "C_HS_A") (class "Default")
      (node (ref "U1") (pin "39") (pinfunction "PWM_UX1_H_39") (pintype "output"))
      (node (ref "U5") (pin "2") (pinfunction "HI_2") (pintype "input"))
    )
    (net (code "29") (name "C_HS_B") (class "Default")
      (node (ref "U1") (pin "41") (pinfunction "PWM_VX2_H_41") (pintype "output"))
      (node (ref "U4") (pin "2") (pinfunction "HI_2") (pintype "input"))
    )
    (net (code "30") (name "C_HS_C") (class "Default")
      (node (ref "U1") (pin "46") (pinfunction "PWM_WY1_H_46") (pintype "output"))
      (node (ref "U3") (pin "2") (pinfunction "HI_2") (pintype "input"))
    )
    (net (code "31") (name "C_HS_D") (class "Default")
      (node (ref "U1") (pin "48") (pinfunction "PWM_Y2_H_48") (pintype "output"))
      (node (ref "U2") (pin "2") (pinfunction "HI_2") (pintype "input"))
    )
    (net (code "32") (name "C_LS_A") (class "Default")
      (node (ref "U1") (pin "40") (pinfunction "PWM_UX1_L_40") (pintype "output"))
      (node (ref "U5") (pin "3") (pinfunction "LI_3") (pintype "input"))
    )
    (net (code "33") (name "C_LS_B") (class "Default")
      (node (ref "U1") (pin "42") (pinfunction "PWM_VX2_L_42") (pintype "output"))
      (node (ref "U4") (pin "3") (pinfunction "LI_3") (pintype "input"))
    )
    (net (code "34") (name "C_LS_C") (class "Default")
      (node (ref "U1") (pin "47") (pinfunction "PWM_WY1_L_47") (pintype "output"))
      (node (ref "U3") (pin "3") (pinfunction "LI_3") (pintype "input"))
    )
    (net (code "35") (name "C_LS_D") (class "Default")
      (node (ref "U1") (pin "49") (pinfunction "PWM_Y2_L_49") (pintype "output"))
      (node (ref "U2") (pin "3") (pinfunction "LI_3") (pintype "input"))
    )
    (net (code "36") (name "DIR") (class "Default")
      (node (ref "JP10") (pin "3") (pinfunction "3_3") (pintype "passive"))
      (node (ref "U1") (pin "56") (pinfunction "DIR_56") (pintype "input"))
    )
    (net (code "37") (name "ENABLE") (class "Default")
      (node (ref "JP7") (pin "2") (pinfunction "2_2") (pintype "passive"))
      (node (ref "R22") (pin "1") (pinfunction "1_1") (pintype "passive"))
      (node (ref "U1") (pin "55") (pinfunction "ENI_55") (pintype "input"))
    )
    (net (code "38") (name "ENC2_A") (class "Default")
      (node (ref "JP9") (pin "2") (pinfunction "2_2") (pintype "passive"))
      (node (ref "U1") (pin "64") (pinfunction "ENC2_A_64") (pintype "input"))
    )
    (net (code "39") (name "ENC2_B") (class "Default")
      (node (ref "JP9") (pin "4") (pinfunction "4_4") (pintype "passive"))
      (node (ref "U1") (pin "65") (pinfunction "ENC2_B_65") (pintype "input"))
    )
    (net (code "40") (name "ENC2_Z") (class "Default")
      (node (ref "JP9") (pin "6") (pinfunction "6_6") (pintype "passive"))
      (node (ref "U1") (pin "66") (pinfunction "ENC2_N_66") (pintype "input"))
    )
    (net (code "41") (name "ENC_A") (class "Default")
      (node (ref "U1") (pin "35") (pinfunction "ENC_A_35") (pintype "input"))
      (node (ref "U19") (pin "6") (pinfunction "3Y_6") (pintype "bidirectional"))
    )
    (net (code "42") (name "ENC_A_5V") (class "Default")
      (node (ref "JP11") (pin "4") (pinfunction "4_4") (pintype "passive"))
      (node (ref "R37") (pin "1") (pinfunction "1_1") (pintype "passive"))
      (node (ref "U19") (pin "5") (pinfunction "3A_5") (pintype "bidirectional"))
    )
    (net (code "43") (name "ENC_B") (class "Default")
      (node (ref "U1") (pin "34") (pinfunction "ENC_B_34") (pintype "input"))
      (node (ref "U19") (pin "4") (pinfunction "2Y_4") (pintype "bidirectional"))
    )
    (net (code "44") (name "ENC_B_5V") (class "Default")
      (node (ref "JP11") (pin "3") (pinfunction "3_3") (pintype "passive"))
      (node (ref "R35") (pin "1") (pinfunction "1_1") (pintype "passive"))
      (node (ref "U19") (pin "3") (pinfunction "2A_3") (pintype "bidirectional"))
    )
    (net (code "45") (name "ENC_Z") (class "Default")
      (node (ref "U1") (pin "33") (pinfunction "ENC_N_33") (pintype "input"))
      (node (ref "U19") (pin "2") (pinfunction "1Y_2") (pintype "bidirectional"))
    )
    (net (code "46") (name "ENC_Z_5V") (class "Default")
      (node (ref "JP11") (pin "2") (pinfunction "2_2") (pintype "passive"))
      (node (ref "R34") (pin "1") (pinfunction "1_1") (pintype "passive"))
      (node (ref "U19") (pin "1") (pinfunction "1A_1") (pintype "bidirectional"))
    )
    (net (code "47") (name "ENO") (class "Default")
      (node (ref "JP1") (pin "1") (pinfunction "1_1") (pintype "passive"))
      (node (ref "U1") (pin "32") (pinfunction "ENO_32") (pintype "output"))
    )
    (net (code "48") (name "FLAG") (class "Default")
      (node (ref "D1") (pin "C") (pinfunction "C_C") (pintype "passive"))
      (node (ref "R3") (pin "2") (pinfunction "2_2") (pintype "passive"))
      (node (ref "X1") (pin "11") (pinfunction "KL_11") (pintype "passive"))
    )
    (net (code "49") (name "GND") (class "Default")
      (node (ref "C1") (pin "1") (pinfunction "1_1") (pintype "passive"))
      (node (ref "C10") (pin "-") (pinfunction "-_-") (pintype "passive"))
      (node (ref "C11") (pin "2") (pinfunction "2_2") (pintype "passive"))
      (node (ref "C12") (pin "2") (pinfunction "2_2") (pintype "passive"))
      (node (ref "C13") (pin "2") (pinfunction "2_2") (pintype "passive"))
      (node (ref "C14") (pin "2") (pinfunction "2_2") (pintype "passive"))
      (node (ref "C15") (pin "2") (pinfunction "2_2") (pintype "passive"))
      (node (ref "C16") (pin "2") (pinfunction "2_2") (pintype "passive"))
      (node (ref "C17") (pin "2") (pinfunction "2_2") (pintype "passive"))
      (node (ref "C18") (pin "2") (pinfunction "2_2") (pintype "passive"))
      (node (ref "C2") (pin "1") (pinfunction "1_1") (pintype "passive"))
      (node (ref "C23") (pin "1") (pinfunction "1_1") (pintype "passive"))
      (node (ref "C24") (pin "2") (pinfunction "2_2") (pintype "passive"))
      (node (ref "C25") (pin "2") (pinfunction "2_2") (pintype "passive"))
      (node (ref "C26") (pin "2") (pinfunction "2_2") (pintype "passive"))
      (node (ref "C29") (pin "1") (pinfunction "1_1") (pintype "passive"))
      (node (ref "C3") (pin "1") (pinfunction "1_1") (pintype "passive"))
      (node (ref "C30") (pin "1") (pinfunction "1_1") (pintype "passive"))
      (node (ref "C31") (pin "1") (pinfunction "1_1") (pintype "passive"))
      (node (ref "C32") (pin "2") (pinfunction "2_2") (pintype "passive"))
      (node (ref "C34") (pin "2") (pinfunction "2_2") (pintype "passive"))
      (node (ref "C35") (pin "1") (pinfunction "1_1") (pintype "passive"))
      (node (ref "C37") (pin "1") (pinfunction "1_1") (pintype "passive"))
      (node (ref "C38") (pin "2") (pinfunction "2_2") (pintype "passive"))
      (node (ref "C39") (pin "2") (pinfunction "2_2") (pintype "passive"))
      (node (ref "C4") (pin "1") (pinfunction "1_1") (pintype "passive"))
      (node (ref "C5") (pin "1") (pinfunction "1_1") (pintype "passive"))
      (node (ref "C6") (pin "1") (pinfunction "1_1") (pintype "passive"))
      (node (ref "C7") (pin "1") (pinfunction "1_1") (pintype "passive"))
      (node (ref "C8") (pin "1") (pinfunction "1_1") (pintype "passive"))
      (node (ref "C9") (pin "-") (pinfunction "-_-") (pintype "passive"))
      (node (ref "D13") (pin "A") (pinfunction "A_A") (pintype "passive"))
      (node (ref "D14") (pin "A") (pinfunction "A_A") (pintype "passive"))
      (node (ref "D15") (pin "A") (pinfunction "A_A") (pintype "passive"))
      (node (ref "H1") (pin "B3,0") (pinfunction "MOUNT_B3,0") (pintype "passive"))
      (node (ref "H2") (pin "B3,0") (pinfunction "MOUNT_B3,0") (pintype "passive"))
      (node (ref "H3") (pin "B3,0") (pinfunction "MOUNT_B3,0") (pintype "passive"))
      (node (ref "H4") (pin "B3,0") (pinfunction "MOUNT_B3,0") (pintype "passive"))
      (node (ref "H5") (pin "B3,0") (pinfunction "MOUNT_B3,0") (pintype "passive"))
      (node (ref "H6") (pin "B3,0") (pinfunction "MOUNT_B3,0") (pintype "passive"))
      (node (ref "JP11") (pin "5") (pinfunction "5_5") (pintype "passive"))
      (node (ref "JP12") (pin "5") (pinfunction "5_5") (pintype "passive"))
      (node (ref "JP2") (pin "1") (pinfunction "1_1") (pintype "passive"))
      (node (ref "JP6") (pin "3") (pinfunction "3_3") (pintype "passive"))
      (node (ref "JP7") (pin "1") (pinfunction "1_1") (pintype "passive"))
      (node (ref "LED1") (pin "C") (pinfunction "C_C") (pintype "passive"))
      (node (ref "R12") (pin "1") (pinfunction "1_1") (pintype "passive"))
      (node (ref "R13") (pin "1") (pinfunction "1_1") (pintype "passive"))
      (node (ref "R14") (pin "1") (pinfunction "1_1") (pintype "passive"))
      (node (ref "R15") (pin "1") (pinfunction "1_1") (pintype "passive"))
      (node (ref "R18") (pin "1") (pinfunction "1_1") (pintype "passive"))
      (node (ref "R20") (pin "1") (pinfunction "1_1") (pintype "passive"))
      (node (ref "R21") (pin "1") (pinfunction "1_1") (pintype "passive"))
      (node (ref "R24") (pin "1") (pinfunction "1_1") (pintype "passive"))
      (node (ref "R26") (pin "1") (pinfunction "1_1") (pintype "passive"))
      (node (ref "R28") (pin "1") (pinfunction "1_1") (pintype "passive"))
      (node (ref "R3") (pin "1") (pinfunction "1_1") (pintype "passive"))
      (node (ref "R31") (pin "1") (pinfunction "1_1") (pintype "passive"))
      (node (ref "R33") (pin "1") (pinfunction "1_1") (pintype "passive"))
      (node (ref "R44") (pin "2") (pinfunction "2_2") (pintype "passive"))
      (node (ref "R46") (pin "1") (pinfunction "1_1") (pintype "passive"))
      (node (ref "U1") (pin "14") (pinfunction "GNDIO2_14") (pintype "power_in"))
      (node (ref "U1") (pin "24") (pinfunction "GNDA_24") (pintype "power_in"))
      (node (ref "U1") (pin "3") (pinfunction "GNDIO1_3") (pintype "power_in"))
      (node (ref "U1") (pin "44") (pinfunction "GNDIO3_44") (pintype "power_in"))
      (node (ref "U1") (pin "53") (pinfunction "GNDIO4_53") (pintype "power_in"))
      (node (ref "U1") (pin "54") (pinfunction "TEST_54") (pintype "input"))
      (node (ref "U1") (pin "59") (pinfunction "PWM_IDLE_H_59") (pintype "input"))
      (node (ref "U1") (pin "60") (pinfunction "PWM_IDLE_L_60") (pintype "input"))
      (node (ref "U1") (pin "62") (pinfunction "GNDIO5_62") (pintype "power_in"))
      (node (ref "U1") (pin "73") (pinfunction "GNDIO6_73") (pintype "power_in"))
      (node (ref "U1") (pin "77") (pinfunction "GNDIO6_77") (pintype "power_in"))
      (node (ref "U11") (pin "1") (pinfunction "S_1") (pintype "passive"))
      (node (ref "U11") (pin "2") (pinfunction "S_2") (pintype "passive"))
      (node (ref "U11") (pin "3") (pinfunction "S_3") (pintype "passive"))
      (node (ref "U13") (pin "1") (pinfunction "S_1") (pintype "passive"))
      (node (ref "U13") (pin "2") (pinfunction "S_2") (pintype "passive"))
      (node (ref "U13") (pin "3") (pinfunction "S_3") (pintype "passive"))
      (node (ref "U14") (pin "1") (pinfunction "GND_1") (pintype "bidirectional"))
      (node (ref "U14") (pin "4") (pinfunction "GND_4") (pintype "bidirectional"))
      (node (ref "U16") (pin "1") (pinfunction "S_1") (pintype "passive"))
      (node (ref "U16") (pin "2") (pinfunction "S_2") (pintype "passive"))
      (node (ref "U16") (pin "3") (pinfunction "S_3") (pintype "passive"))
      (node (ref "U17") (pin "1") (pinfunction "S_1") (pintype "passive"))
      (node (ref "U17") (pin "2") (pinfunction "S_2") (pintype "passive"))
      (node (ref "U17") (pin "3") (pinfunction "S_3") (pintype "passive"))
      (node (ref "U18") (pin "11") (pinfunction "GND_11") (pintype "bidirectional"))
      (node (ref "U19") (pin "7") (pinfunction "GND_7") (pintype "bidirectional"))
      (node (ref "U2") (pin "4") (pinfunction "VSS_4") (pintype "power_in"))
      (node (ref "U2") (pin "9") (pinfunction "EP_9") (pintype "power_in"))
      (node (ref "U20") (pin "2") (pinfunction "GND_2") (pintype "bidirectional"))
      (node (ref "U21") (pin "1") (pinfunction "ADJ_1") (pintype "input"))
      (node (ref "U23") (pin "3") (pinfunction "SGND_3") (pintype "power_in"))
      (node (ref "U23") (pin "6") (pinfunction "GND_6") (pintype "power_in"))
      (node (ref "U24") (pin "2") (pinfunction "GND_2") (pintype "bidirectional"))
      (node (ref "U3") (pin "4") (pinfunction "VSS_4") (pintype "power_in"))
      (node (ref "U3") (pin "9") (pinfunction "EP_9") (pintype "power_in"))
      (node (ref "U4") (pin "4") (pinfunction "VSS_4") (pintype "power_in"))
      (node (ref "U4") (pin "9") (pinfunction "EP_9") (pintype "power_in"))
      (node (ref "U5") (pin "4") (pinfunction "VSS_4") (pintype "power_in"))
      (node (ref "U5") (pin "9") (pinfunction "EP_9") (pintype "power_in"))
      (node (ref "U6") (pin "5") (pinfunction "GND_5") (pintype "passive"))
      (node (ref "U7") (pin "5") (pinfunction "GND_5") (pintype "passive"))
      (node (ref "U9") (pin "1") (pinfunction "S_1") (pintype "passive"))
      (node (ref "U9") (pin "2") (pinfunction "S_2") (pintype "passive"))
      (node (ref "U9") (pin "3") (pinfunction "S_3") (pintype "passive"))
      (node (ref "X1") (pin "1") (pinfunction "KL_1") (pintype "passive"))
      (node (ref "X2") (pin "1") (pinfunction "1_1") (pintype "passive"))
      (node (ref "Y1") (pin "2") (pinfunction "GND_2") (pintype "power_in"))
    )
    (net (code "50") (name "GPIO0") (class "Default")
      (node (ref "JP8") (pin "1") (pinfunction "1_1") (pintype "passive"))
      (node (ref "U1") (pin "70") (pinfunction "GPIO0/ADC_I0_MCD_70") (pintype "bidirectional"))
    )
    (net (code "51") (name "GPIO1") (class "Default")
      (node (ref "JP8") (pin "2") (pinfunction "2_2") (pintype "passive"))
      (node (ref "U1") (pin "71") (pinfunction "GPIO1/ADC_I1_MCD_71") (pintype "bidirectional"))
    )
    (net (code "52") (name "GPIO2") (class "Default")
      (node (ref "JP8") (pin "3") (pinfunction "3_3") (pintype "passive"))
      (node (ref "U1") (pin "74") (pinfunction "GPIO2/ADC_VM_MCD_74") (pintype "bidirectional"))
    )
    (net (code "53") (name "GPIO3") (class "Default")
      (node (ref "JP8") (pin "4") (pinfunction "4_4") (pintype "passive"))
      (node (ref "U1") (pin "75") (pinfunction "GPIO3/AGPI_A_MCD/DBGSPI_NSCS_75") (pintype "bidirectional"))
    )
    (net (code "54") (name "GPIO4") (class "Default")
      (node (ref "JP8") (pin "5") (pinfunction "5_5") (pintype "passive"))
      (node (ref "U1") (pin "76") (pinfunction "GPIO4/AGPI_B_MCD/DBGSPI_SCK_76") (pintype "bidirectional"))
    )
    (net (code "55") (name "GPIO5") (class "Default")
      (node (ref "JP8") (pin "6") (pinfunction "6_6") (pintype "passive"))
      (node (ref "U1") (pin "1") (pinfunction "GPIO5/AENC_UX_MCD/DBGSPI_MOSI_1") (pintype "bidirectional"))
    )
    (net (code "56") (name "GPIO6") (class "Default")
      (node (ref "JP8") (pin "7") (pinfunction "7_7") (pintype "passive"))
      (node (ref "U1") (pin "4") (pinfunction "GPIO6/AENC_VN_MCD/DBGSPI_MISO_4") (pintype "bidirectional"))
    )
    (net (code "57") (name "GPIO7") (class "Default")
      (node (ref "JP8") (pin "8") (pinfunction "8_8") (pintype "passive"))
      (node (ref "U1") (pin "5") (pinfunction "GPIO7/AENC_WY_MCD/DBGSPI_TRG_5") (pintype "bidirectional"))
    )
    (net (code "58") (name "G_HS_A") (class "Default")
      (node (ref "D6") (pin "C") (pinfunction "C_C") (pintype "passive"))
      (node (ref "R10") (pin "1") (pinfunction "1_1") (pintype "passive"))
      (node (ref "U8") (pin "4") (pinfunction "G_4") (pintype "passive"))
    )
    (net (code "59") (name "G_HS_B") (class "Default")
      (node (ref "D7") (pin "C") (pinfunction "C_C") (pintype "passive"))
      (node (ref "R8") (pin "1") (pinfunction "1_1") (pintype "passive"))
      (node (ref "U10") (pin "4") (pinfunction "G_4") (pintype "passive"))
    )
    (net (code "60") (name "G_HS_C") (class "Default")
      (node (ref "D8") (pin "C") (pinfunction "C_C") (pintype "passive"))
      (node (ref "R6") (pin "1") (pinfunction "1_1") (pintype "passive"))
      (node (ref "U12") (pin "4") (pinfunction "G_4") (pintype "passive"))
    )
    (net (code "61") (name "G_HS_D") (class "Default")
      (node (ref "D11") (pin "C") (pinfunction "C_C") (pintype "passive"))
      (node (ref "R4") (pin "1") (pinfunction "1_1") (pintype "passive"))
      (node (ref "U15") (pin "4") (pinfunction "G_4") (pintype "passive"))
    )
    (net (code "62") (name "G_LS_A") (class "Default")
      (node (ref "R11") (pin "1") (pinfunction "1_1") (pintype "passive"))
      (node (ref "R12") (pin "2") (pinfunction "2_2") (pintype "passive"))
      (node (ref "U9") (pin "4") (pinfunction "G_4") (pintype "passive"))
    )
    (net (code "63") (name "G_LS_B") (class "Default")
      (node (ref "R13") (pin "2") (pinfunction "2_2") (pintype "passive"))
      (node (ref "R9") (pin "1") (pinfunction "1_1") (pintype "passive"))
      (node (ref "U11") (pin "4") (pinfunction "G_4") (pintype "passive"))
    )
    (net (code "64") (name "G_LS_C") (class "Default")
      (node (ref "R14") (pin "2") (pinfunction "2_2") (pintype "passive"))
      (node (ref "R7") (pin "1") (pinfunction "1_1") (pintype "passive"))
      (node (ref "U13") (pin "4") (pinfunction "G_4") (pintype "passive"))
    )
    (net (code "65") (name "G_LS_D") (class "Default")
      (node (ref "R20") (pin "2") (pinfunction "2_2") (pintype "passive"))
      (node (ref "R5") (pin "1") (pinfunction "1_1") (pintype "passive"))
      (node (ref "U16") (pin "4") (pinfunction "G_4") (pintype "passive"))
    )
    (net (code "66") (name "HALL_UX") (class "Default")
      (node (ref "U1") (pin "38") (pinfunction "HALL_UX_38") (pintype "input"))
      (node (ref "U19") (pin "12") (pinfunction "6Y_12") (pintype "bidirectional"))
    )
    (net (code "67") (name "HALL_UX_5V") (class "Default")
      (node (ref "C29") (pin "2") (pinfunction "2_2") (pintype "passive"))
      (node (ref "R40") (pin "1") (pinfunction "1_1") (pintype "passive"))
      (node (ref "U19") (pin "13") (pinfunction "6A_13") (pintype "bidirectional"))
    )
    (net (code "68") (name "HALL_V") (class "Default")
      (node (ref "U1") (pin "37") (pinfunction "HALL_V_37") (pintype "input"))
      (node (ref "U19") (pin "10") (pinfunction "5Y_10") (pintype "bidirectional"))
    )
    (net (code "69") (name "HALL_V_5V") (class "Default")
      (node (ref "C30") (pin "2") (pinfunction "2_2") (pintype "passive"))
      (node (ref "R41") (pin "1") (pinfunction "1_1") (pintype "passive"))
      (node (ref "U19") (pin "11") (pinfunction "5A_11") (pintype "bidirectional"))
    )
    (net (code "70") (name "HALL_WY") (class "Default")
      (node (ref "U1") (pin "36") (pinfunction "HALL_WY_36") (pintype "input"))
      (node (ref "U19") (pin "8") (pinfunction "4Y_8") (pintype "bidirectional"))
    )
    (net (code "71") (name "HALL_WY_5V") (class "Default")
      (node (ref "C31") (pin "2") (pinfunction "2_2") (pintype "passive"))
      (node (ref "R42") (pin "1") (pinfunction "1_1") (pintype "passive"))
      (node (ref "U19") (pin "9") (pinfunction "4A_9") (pintype "bidirectional"))
    )
    (net (code "72") (name "INPUT_GATE") (class "Default")
      (node (ref "U20") (pin "5") (pinfunction "GATE_5") (pintype "bidirectional"))
      (node (ref "U22") (pin "4") (pinfunction "G_4") (pintype "passive"))
    )
    (net (code "73") (name "MISO") (class "Default")
      (node (ref "U1") (pin "9") (pinfunction "SPI_MISO_9") (pintype "output"))
      (node (ref "X1") (pin "6") (pinfunction "KL_6") (pintype "passive"))
    )
    (net (code "74") (name "MOSI") (class "Default")
      (node (ref "U1") (pin "8") (pinfunction "SPI_MOSI_8") (pintype "input"))
      (node (ref "X1") (pin "5") (pinfunction "KL_5") (pintype "passive"))
    )
    (net (code "75") (name "MOT_A") (class "Default")
      (node (ref "C22") (pin "2") (pinfunction "2_2") (pintype "passive"))
      (node (ref "D6") (pin "A") (pinfunction "A_A") (pintype "passive"))
      (node (ref "U5") (pin "6") (pinfunction "HS_6") (pintype "input"))
      (node (ref "U6") (pin "1") (pinfunction "IN+_2_1") (pintype "input"))
      (node (ref "U6") (pin "2") (pinfunction "IN+_2") (pintype "input"))
      (node (ref "U8") (pin "1") (pinfunction "S_1") (pintype "passive"))
      (node (ref "U8") (pin "2") (pinfunction "S_2") (pintype "passive"))
      (node (ref "U8") (pin "3") (pinfunction "S_3") (pintype "passive"))
      (node (ref "U9") (pin "5") (pinfunction "D_5") (pintype "passive"))
    )
    (net (code "76") (name "MOT_A_OUT") (class "Default")
      (node (ref "U6") (pin "3") (pinfunction "IN-_2_3") (pintype "input"))
      (node (ref "U6") (pin "4") (pinfunction "IN-_4") (pintype "input"))
      (node (ref "X3") (pin "1") (pinfunction "1_1") (pintype "passive"))
    )
    (net (code "77") (name "MOT_B") (class "Default")
      (node (ref "C21") (pin "2") (pinfunction "2_2") (pintype "passive"))
      (node (ref "D7") (pin "A") (pinfunction "A_A") (pintype "passive"))
      (node (ref "U10") (pin "1") (pinfunction "S_1") (pintype "passive"))
      (node (ref "U10") (pin "2") (pinfunction "S_2") (pintype "passive"))
      (node (ref "U10") (pin "3") (pinfunction "S_3") (pintype "passive"))
      (node (ref "U11") (pin "5") (pinfunction "D_5") (pintype "passive"))
      (node (ref "U4") (pin "6") (pinfunction "HS_6") (pintype "input"))
      (node (ref "X3") (pin "2") (pinfunction "1_2") (pintype "passive"))
    )
    (net (code "78") (name "MOT_C") (class "Default")
      (node (ref "C20") (pin "2") (pinfunction "2_2") (pintype "passive"))
      (node (ref "D8") (pin "A") (pinfunction "A_A") (pintype "passive"))
      (node (ref "U12") (pin "1") (pinfunction "S_1") (pintype "passive"))
      (node (ref "U12") (pin "2") (pinfunction "S_2") (pintype "passive"))
      (node (ref "U12") (pin "3") (pinfunction "S_3") (pintype "passive"))
      (node (ref "U13") (pin "5") (pinfunction "D_5") (pintype "passive"))
      (node (ref "U3") (pin "6") (pinfunction "HS_6") (pintype "input"))
      (node (ref "U7") (pin "1") (pinfunction "IN+_2_1") (pintype "input"))
      (node (ref "U7") (pin "2") (pinfunction "IN+_2") (pintype "input"))
    )
    (net (code "79") (name "MOT_C_OUT") (class "Default")
      (node (ref "U7") (pin "3") (pinfunction "IN-_2_3") (pintype "input"))
      (node (ref "U7") (pin "4") (pinfunction "IN-_4") (pintype "input"))
      (node (ref "X3") (pin "3") (pinfunction "1_3") (pintype "passive"))
    )
    (net (code "80") (name "MOT_D") (class "Default")
      (node (ref "C19") (pin "2") (pinfunction "2_2") (pintype "passive"))
      (node (ref "D11") (pin "A") (pinfunction "A_A") (pintype "passive"))
      (node (ref "U15") (pin "1") (pinfunction "S_1") (pintype "passive"))
      (node (ref "U15") (pin "2") (pinfunction "S_2") (pintype "passive"))
      (node (ref "U15") (pin "3") (pinfunction "S_3") (pintype "passive"))
      (node (ref "U16") (pin "5") (pinfunction "D_5") (pintype "passive"))
      (node (ref "U2") (pin "6") (pinfunction "HS_6") (pintype "input"))
      (node (ref "X3") (pin "4") (pinfunction "1_4") (pintype "passive"))
    )
    (net (code "81") (name "Net-(JP12-Pad2)") (class "Default")
      (node (ref "JP12") (pin "2") (pinfunction "2_2") (pintype "passive"))
      (node (ref "R39") (pin "1") (pinfunction "1_1") (pintype "passive"))
      (node (ref "R42") (pin "2") (pinfunction "2_2") (pintype "passive"))
    )
    (net (code "82") (name "Net-(JP12-Pad3)") (class "Default")
      (node (ref "JP12") (pin "3") (pinfunction "3_3") (pintype "passive"))
      (node (ref "R38") (pin "1") (pinfunction "1_1") (pintype "passive"))
      (node (ref "R41") (pin "2") (pinfunction "2_2") (pintype "passive"))
    )
    (net (code "83") (name "Net-(JP12-Pad4)") (class "Default")
      (node (ref "JP12") (pin "4") (pinfunction "4_4") (pintype "passive"))
      (node (ref "R36") (pin "1") (pinfunction "1_1") (pintype "passive"))
      (node (ref "R40") (pin "2") (pinfunction "2_2") (pintype "passive"))
    )
    (net (code "84") (name "Net-(LED1-PadA)") (class "Default")
      (node (ref "LED1") (pin "A") (pinfunction "A_A") (pintype "passive"))
      (node (ref "R29") (pin "1") (pinfunction "1_1") (pintype "passive"))
    )
    (net (code "85") (name "Net-(U1B-STATUS)") (class "Default")
      (node (ref "D1") (pin "A") (pinfunction "A_A") (pintype "passive"))
      (node (ref "U1") (pin "12") (pinfunction "STATUS_12") (pintype "output"))
    )
    (net (code "86") (name "Net-(U1B-VCCCORE1)") (class "Default")
      (node (ref "C1") (pin "2") (pinfunction "2_2") (pintype "passive"))
      (node (ref "C3") (pin "2") (pinfunction "2_2") (pintype "passive"))
      (node (ref "C4") (pin "2") (pinfunction "2_2") (pintype "passive"))
      (node (ref "U1") (pin "15") (pinfunction "VCCCORE1_15") (pintype "power_in"))
      (node (ref "U1") (pin "45") (pinfunction "VCCCORE2_45") (pintype "power_in"))
      (node (ref "U1") (pin "63") (pinfunction "VCCCORE3_63") (pintype "power_in"))
    )
    (net (code "87") (name "Net-(U2-HB)") (class "Default")
      (node (ref "C19") (pin "1") (pinfunction "1_1") (pintype "passive"))
      (node (ref "D2") (pin "C") (pinfunction "C_C") (pintype "passive"))
      (node (ref "U2") (pin "8") (pinfunction "HB_8") (pintype "input"))
    )
    (net (code "88") (name "Net-(U2-HO)") (class "Default")
      (node (ref "R4") (pin "2") (pinfunction "2_2") (pintype "passive"))
      (node (ref "U2") (pin "7") (pinfunction "HO_7") (pintype "output"))
    )
    (net (code "89") (name "Net-(U2-LO)") (class "Default")
      (node (ref "R5") (pin "2") (pinfunction "2_2") (pintype "passive"))
      (node (ref "U2") (pin "5") (pinfunction "LO_5") (pintype "output"))
    )
    (net (code "90") (name "Net-(U3-HB)") (class "Default")
      (node (ref "C20") (pin "1") (pinfunction "1_1") (pintype "passive"))
      (node (ref "D3") (pin "C") (pinfunction "C_C") (pintype "passive"))
      (node (ref "U3") (pin "8") (pinfunction "HB_8") (pintype "input"))
    )
    (net (code "91") (name "Net-(U3-HO)") (class "Default")
      (node (ref "R6") (pin "2") (pinfunction "2_2") (pintype "passive"))
      (node (ref "U3") (pin "7") (pinfunction "HO_7") (pintype "output"))
    )
    (net (code "92") (name "Net-(U3-LO)") (class "Default")
      (node (ref "R7") (pin "2") (pinfunction "2_2") (pintype "passive"))
      (node (ref "U3") (pin "5") (pinfunction "LO_5") (pintype "output"))
    )
    (net (code "93") (name "Net-(U4-HB)") (class "Default")
      (node (ref "C21") (pin "1") (pinfunction "1_1") (pintype "passive"))
      (node (ref "D4") (pin "C") (pinfunction "C_C") (pintype "passive"))
      (node (ref "U4") (pin "8") (pinfunction "HB_8") (pintype "input"))
    )
    (net (code "94") (name "Net-(U4-HO)") (class "Default")
      (node (ref "R8") (pin "2") (pinfunction "2_2") (pintype "passive"))
      (node (ref "U4") (pin "7") (pinfunction "HO_7") (pintype "output"))
    )
    (net (code "95") (name "Net-(U4-LO)") (class "Default")
      (node (ref "R9") (pin "2") (pinfunction "2_2") (pintype "passive"))
      (node (ref "U4") (pin "5") (pinfunction "LO_5") (pintype "output"))
    )
    (net (code "96") (name "Net-(U5-HB)") (class "Default")
      (node (ref "C22") (pin "1") (pinfunction "1_1") (pintype "passive"))
      (node (ref "D5") (pin "C") (pinfunction "C_C") (pintype "passive"))
      (node (ref "U5") (pin "8") (pinfunction "HB_8") (pintype "input"))
    )
    (net (code "97") (name "Net-(U5-HO)") (class "Default")
      (node (ref "R10") (pin "2") (pinfunction "2_2") (pintype "passive"))
      (node (ref "U5") (pin "7") (pinfunction "HO_7") (pintype "output"))
    )
    (net (code "98") (name "Net-(U5-LO)") (class "Default")
      (node (ref "R11") (pin "2") (pinfunction "2_2") (pintype "passive"))
      (node (ref "U5") (pin "5") (pinfunction "LO_5") (pintype "output"))
    )
    (net (code "99") (name "Net-(U20-VCAP)") (class "Default")
      (node (ref "C33") (pin "1") (pinfunction "1_1") (pintype "passive"))
      (node (ref "U20") (pin "1") (pinfunction "VCAP_1") (pintype "bidirectional"))
    )
    (net (code "100") (name "Net-(U23-BST)") (class "Default")
      (node (ref "C36") (pin "1") (pinfunction "1_1") (pintype "passive"))
      (node (ref "U23") (pin "1") (pinfunction "BST_1") (pintype "passive"))
    )
    (net (code "101") (name "Net-(U23-LX)") (class "Default")
      (node (ref "C36") (pin "2") (pinfunction "2_2") (pintype "passive"))
      (node (ref "D14") (pin "C") (pinfunction "C_C") (pintype "passive"))
      (node (ref "L1") (pin "1") (pinfunction "1_1") (pintype "passive"))
      (node (ref "U23") (pin "8") (pinfunction "LX_8") (pintype "passive"))
    )
    (net (code "102") (name "Net-(U23-ON{slash}~{OFF})") (class "Default")
      (node (ref "R43") (pin "1") (pinfunction "1_1") (pintype "passive"))
      (node (ref "R44") (pin "1") (pinfunction "1_1") (pintype "passive"))
      (node (ref "U23") (pin "5") (pinfunction "ON/~{OFF}_5") (pintype "input"))
    )
    (net (code "103") (name "Net-(U23-VD)") (class "Default")
      (node (ref "C35") (pin "2") (pinfunction "2_2") (pintype "passive"))
      (node (ref "U23") (pin "2") (pinfunction "VD_2") (pintype "power_in"))
    )
    (net (code "104") (name "Net-(U24-FB)") (class "Default")
      (node (ref "R45") (pin "1") (pinfunction "1_1") (pintype "passive"))
      (node (ref "R46") (pin "2") (pinfunction "2_2") (pintype "passive"))
      (node (ref "U24") (pin "3") (pinfunction "FB_3") (pintype "bidirectional"))
    )
    (net (code "105") (name "Net-(U24-SW)") (class "Default")
      (node (ref "D16") (pin "A") (pinfunction "A_A") (pintype "passive"))
      (node (ref "L2") (pin "2") (pinfunction "2_2") (pintype "passive"))
      (node (ref "U24") (pin "1") (pinfunction "SW_1") (pintype "bidirectional"))
    )
    (net (code "106") (name "Net-(X1H-KL)") (class "Default")
      (node (ref "R22") (pin "2") (pinfunction "2_2") (pintype "passive"))
      (node (ref "X1") (pin "16") (pinfunction "KL_16") (pintype "passive"))
    )
    (net (code "107") (name "Net-(X1I-KL)") (class "Default")
      (node (ref "JP5") (pin "1") (pinfunction "1_1") (pintype "passive"))
      (node (ref "X1") (pin "2") (pinfunction "KL_2") (pintype "passive"))
    )
    (net (code "108") (name "Net-(X1K-KL)") (class "Default")
      (node (ref "SJ6") (pin "1") (pinfunction "1_1") (pintype "passive"))
      (node (ref "X1") (pin "4") (pinfunction "KL_4") (pintype "passive"))
    )
    (net (code "109") (name "PWM_I") (class "Default")
      (node (ref "JP10") (pin "1") (pinfunction "1_1") (pintype "passive"))
      (node (ref "U1") (pin "58") (pinfunction "PWM_I_58") (pintype "input"))
    )
    (net (code "110") (name "REF_H") (class "Default")
      (node (ref "JP9") (pin "3") (pinfunction "3_3") (pintype "passive"))
      (node (ref "U1") (pin "68") (pinfunction "REF_H_68") (pintype "input"))
    )
    (net (code "111") (name "REF_L") (class "Default")
      (node (ref "JP9") (pin "1") (pinfunction "1_1") (pintype "passive"))
      (node (ref "U1") (pin "67") (pinfunction "REF_L_67") (pintype "input"))
    )
    (net (code "112") (name "REF_R") (class "Default")
      (node (ref "JP9") (pin "5") (pinfunction "5_5") (pintype "passive"))
      (node (ref "U1") (pin "69") (pinfunction "REF_R_69") (pintype "input"))
    )
    (net (code "113") (name "RESET") (class "Default")
      (node (ref "R2") (pin "1") (pinfunction "1_1") (pintype "passive"))
      (node (ref "U1") (pin "50") (pinfunction "NRST_50") (pintype "input"))
      (node (ref "X1") (pin "3") (pinfunction "KL_3") (pintype "passive"))
    )
    (net (code "114") (name "RES_FET") (class "Default")
      (node (ref "D12") (pin "A") (pinfunction "A_A") (pintype "passive"))
      (node (ref "D13") (pin "C") (pinfunction "C_C") (pintype "passive"))
      (node (ref "U17") (pin "5") (pinfunction "D_5") (pintype "passive"))
      (node (ref "X2") (pin "4") (pinfunction "1_4") (pintype "passive"))
    )
    (net (code "115") (name "SCK") (class "Default")
      (node (ref "U1") (pin "7") (pinfunction "SPI_SCK_7") (pintype "input"))
      (node (ref "X1") (pin "8") (pinfunction "KL_8") (pintype "passive"))
    )
    (net (code "116") (name "SENSE_A") (class "Default")
      (node (ref "C27") (pin "2") (pinfunction "2_2") (pintype "passive"))
      (node (ref "U1") (pin "16") (pinfunction "ADC_I0_POS_16") (pintype "input"))
      (node (ref "U6") (pin "7") (pinfunction "VOUT_7") (pintype "output"))
    )
    (net (code "117") (name "SENSE_C") (class "Default")
      (node (ref "C28") (pin "2") (pinfunction "2_2") (pintype "passive"))
      (node (ref "U1") (pin "18") (pinfunction "ADC_I1_POS_18") (pintype "input"))
      (node (ref "U7") (pin "7") (pinfunction "VOUT_7") (pintype "output"))
    )
    (net (code "118") (name "STEP") (class "Default")
      (node (ref "JP10") (pin "2") (pinfunction "2_2") (pintype "passive"))
      (node (ref "U1") (pin "57") (pinfunction "STP_57") (pintype "input"))
    )
    (net (code "119") (name "TH_FET") (class "Default")
      (node (ref "R30") (pin "1") (pinfunction "1_1") (pintype "passive"))
      (node (ref "R31") (pin "2") (pinfunction "2_2") (pintype "passive"))
      (node (ref "U18") (pin "3") (pinfunction "INA+_3") (pintype "bidirectional"))
    )
    (net (code "120") (name "UART_RX") (class "Default")
      (node (ref "JP6") (pin "1") (pinfunction "1_1") (pintype "passive"))
      (node (ref "U1") (pin "10") (pinfunction "UART_RXD_10") (pintype "input"))
    )
    (net (code "121") (name "UART_TX") (class "Default")
      (node (ref "JP6") (pin "2") (pinfunction "2_2") (pintype "passive"))
      (node (ref "U1") (pin "11") (pinfunction "UART_TXD_11") (pintype "output"))
    )
    (net (code "122") (name "V+") (class "Default")
      (node (ref "C10") (pin "+") (pinfunction "+_+") (pintype "passive"))
      (node (ref "C11") (pin "1") (pinfunction "1_1") (pintype "passive"))
      (node (ref "C12") (pin "1") (pinfunction "1_1") (pintype "passive"))
      (node (ref "C13") (pin "1") (pinfunction "1_1") (pintype "passive"))
      (node (ref "C14") (pin "1") (pinfunction "1_1") (pintype "passive"))
      (node (ref "C37") (pin "2") (pinfunction "2_2") (pintype "passive"))
      (node (ref "C9") (pin "+") (pinfunction "+_+") (pintype "passive"))
      (node (ref "D12") (pin "C") (pinfunction "C_C") (pintype "passive"))
      (node (ref "R23") (pin "2") (pinfunction "2_2") (pintype "passive"))
      (node (ref "R25") (pin "2") (pinfunction "2_2") (pintype "passive"))
      (node (ref "R43") (pin "2") (pinfunction "2_2") (pintype "passive"))
      (node (ref "U10") (pin "5") (pinfunction "D_5") (pintype "passive"))
      (node (ref "U12") (pin "5") (pinfunction "D_5") (pintype "passive"))
      (node (ref "U15") (pin "5") (pinfunction "D_5") (pintype "passive"))
      (node (ref "U20") (pin "4") (pinfunction "CATHODE_4") (pintype "bidirectional"))
      (node (ref "U22") (pin "5") (pinfunction "D_5") (pintype "passive"))
      (node (ref "U23") (pin "7") (pinfunction "VIN_7") (pintype "power_in"))
      (node (ref "U8") (pin "5") (pinfunction "D_5") (pintype "passive"))
      (node (ref "X2") (pin "2") (pinfunction "1_2") (pintype "passive"))
    )
    (net (code "123") (name "V_EXT") (class "Default")
      (node (ref "R27") (pin "1") (pinfunction "1_1") (pintype "passive"))
      (node (ref "R28") (pin "2") (pinfunction "2_2") (pintype "passive"))
      (node (ref "X1") (pin "13") (pinfunction "KL_13") (pintype "passive"))
    )
    (net (code "124") (name "V_GD") (class "Default")
      (node (ref "C39") (pin "1") (pinfunction "1_1") (pintype "passive"))
      (node (ref "C5") (pin "2") (pinfunction "2_2") (pintype "passive"))
      (node (ref "C6") (pin "2") (pinfunction "2_2") (pintype "passive"))
      (node (ref "C7") (pin "2") (pinfunction "2_2") (pintype "passive"))
      (node (ref "C8") (pin "2") (pinfunction "2_2") (pintype "passive"))
      (node (ref "D16") (pin "C") (pinfunction "C_C") (pintype "passive"))
      (node (ref "D2") (pin "A") (pinfunction "A_A") (pintype "passive"))
      (node (ref "D3") (pin "A") (pinfunction "A_A") (pintype "passive"))
      (node (ref "D4") (pin "A") (pinfunction "A_A") (pintype "passive"))
      (node (ref "D5") (pin "A") (pinfunction "A_A") (pintype "passive"))
      (node (ref "JP4") (pin "1") (pinfunction "1_1") (pintype "passive"))
      (node (ref "R45") (pin "2") (pinfunction "2_2") (pintype "passive"))
      (node (ref "U14") (pin "2") (pinfunction "VDD_2") (pintype "bidirectional"))
      (node (ref "U2") (pin "1") (pinfunction "VDD_1") (pintype "power_in"))
      (node (ref "U3") (pin "1") (pinfunction "VDD_1") (pintype "power_in"))
      (node (ref "U4") (pin "1") (pinfunction "VDD_1") (pintype "power_in"))
      (node (ref "U5") (pin "1") (pinfunction "VDD_1") (pintype "power_in"))
    )
    (net (code "125") (name "V_INT") (class "Default")
      (node (ref "R25") (pin "1") (pinfunction "1_1") (pintype "passive"))
      (node (ref "R26") (pin "2") (pinfunction "2_2") (pintype "passive"))
      (node (ref "X1") (pin "14") (pinfunction "KL_14") (pintype "passive"))
    )
    (net (code "126") (name "V_INT_TMC") (class "Default")
      (node (ref "U1") (pin "20") (pinfunction "ADC_VM_20") (pintype "input"))
      (node (ref "U18") (pin "12") (pinfunction "IND+_12") (pintype "bidirectional"))
      (node (ref "U18") (pin "8") (pinfunction "OUTC_8") (pintype "bidirectional"))
      (node (ref "U18") (pin "9") (pinfunction "INC-_9") (pintype "bidirectional"))
    )
    (net (code "127") (name "V_INT_TMC_RAW") (class "Default")
      (node (ref "R23") (pin "1") (pinfunction "1_1") (pintype "passive"))
      (node (ref "R24") (pin "2") (pinfunction "2_2") (pintype "passive"))
      (node (ref "U18") (pin "10") (pinfunction "INC+_10") (pintype "bidirectional"))
    )
    (net (code "128") (name "V_MOT_IN") (class "Default")
      (node (ref "C33") (pin "2") (pinfunction "2_2") (pintype "passive"))
      (node (ref "R27") (pin "2") (pinfunction "2_2") (pintype "passive"))
      (node (ref "U20") (pin "3") (pinfunction "EN_3") (pintype "bidirectional"))
      (node (ref "U20") (pin "6") (pinfunction "ANODE_6") (pintype "bidirectional"))
      (node (ref "U22") (pin "1") (pinfunction "S_1") (pintype "passive"))
      (node (ref "U22") (pin "2") (pinfunction "S_2") (pintype "passive"))
      (node (ref "U22") (pin "3") (pinfunction "S_3") (pintype "passive"))
      (node (ref "X2") (pin "3") (pinfunction "1_3") (pintype "passive"))
    )
    (net (code "129") (name "unconnected-(X1G-KL-Pad15)") (class "Default")
      (node (ref "X1") (pin "15") (pinfunction "KL_15") (pintype "passive"))
    )
    (net (code "130") (name "unconnected-(Y1-TRI_STATE-Pad1)") (class "Default")
      (node (ref "Y1") (pin "1") (pinfunction "TRI_STATE_1") (pintype "input"))
    )
  )
)
